# HIVE_dev_sc.net
KiCad netlist of a schematic drawn in EAGLE
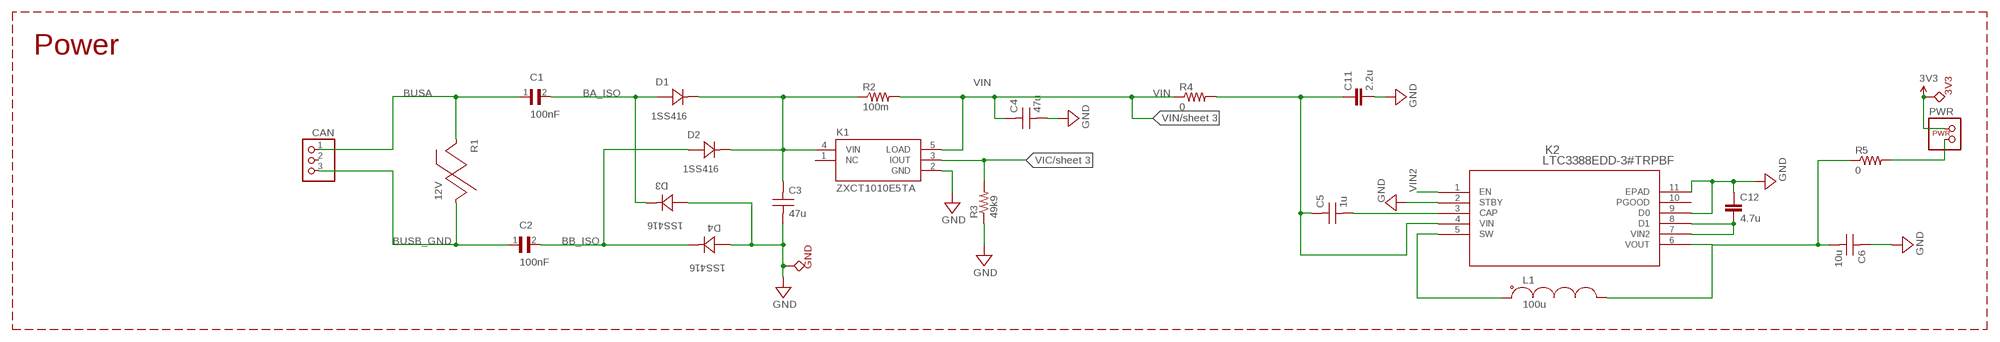
[diagram p0: schematic, sheet 1]
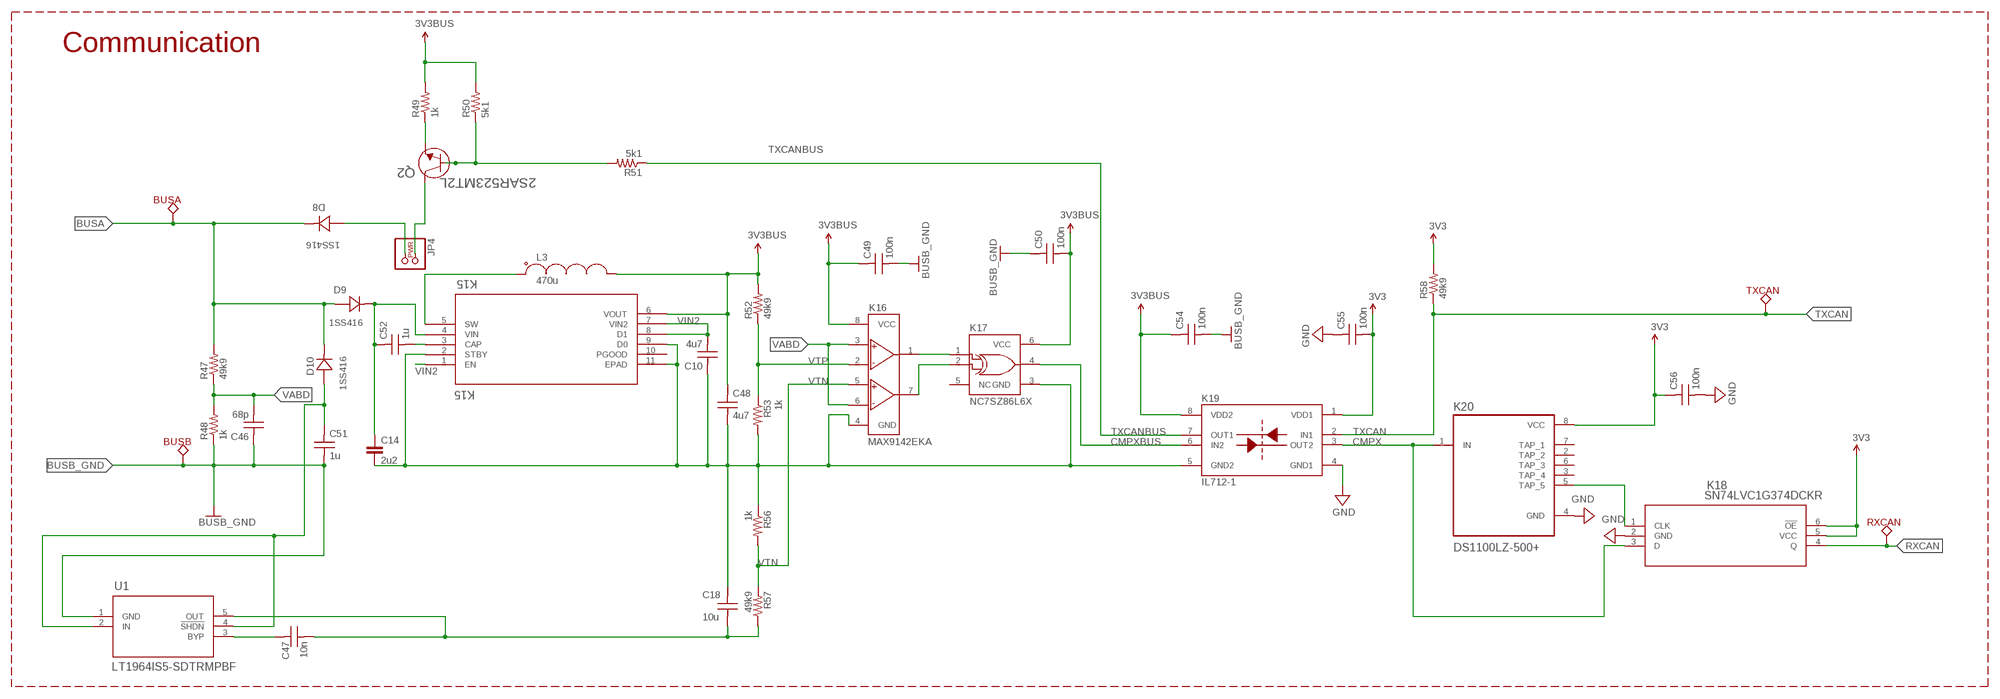
[diagram p1: schematic, sheet 2]
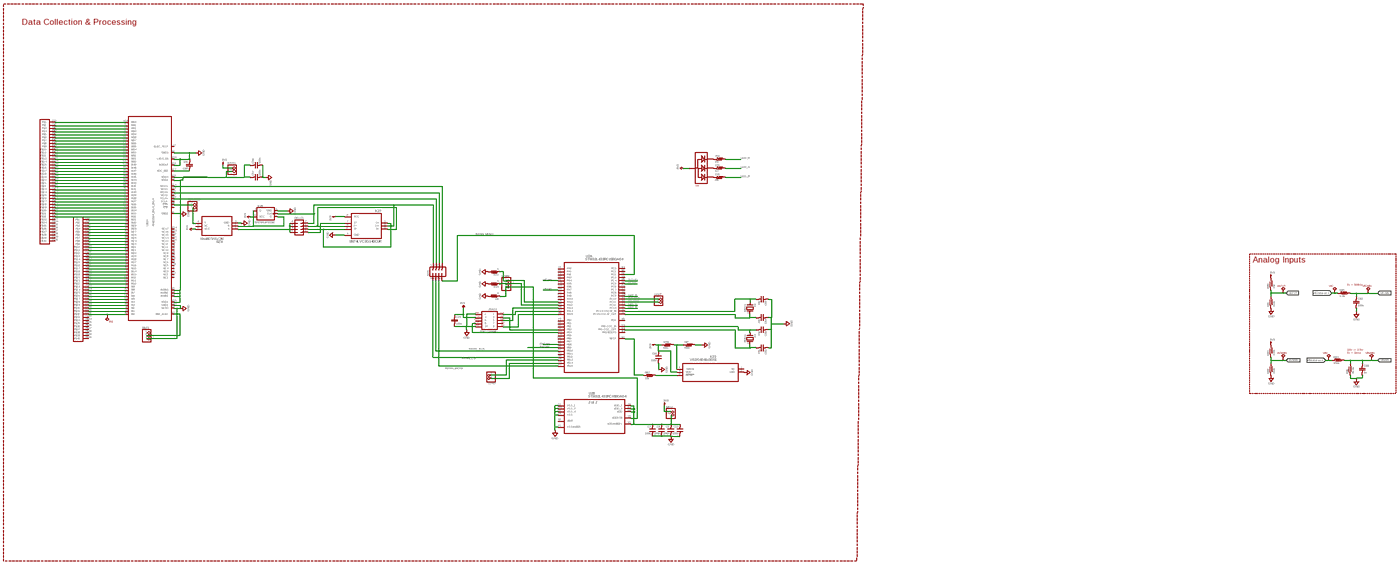
[diagram p2: schematic, sheet 3, overview]
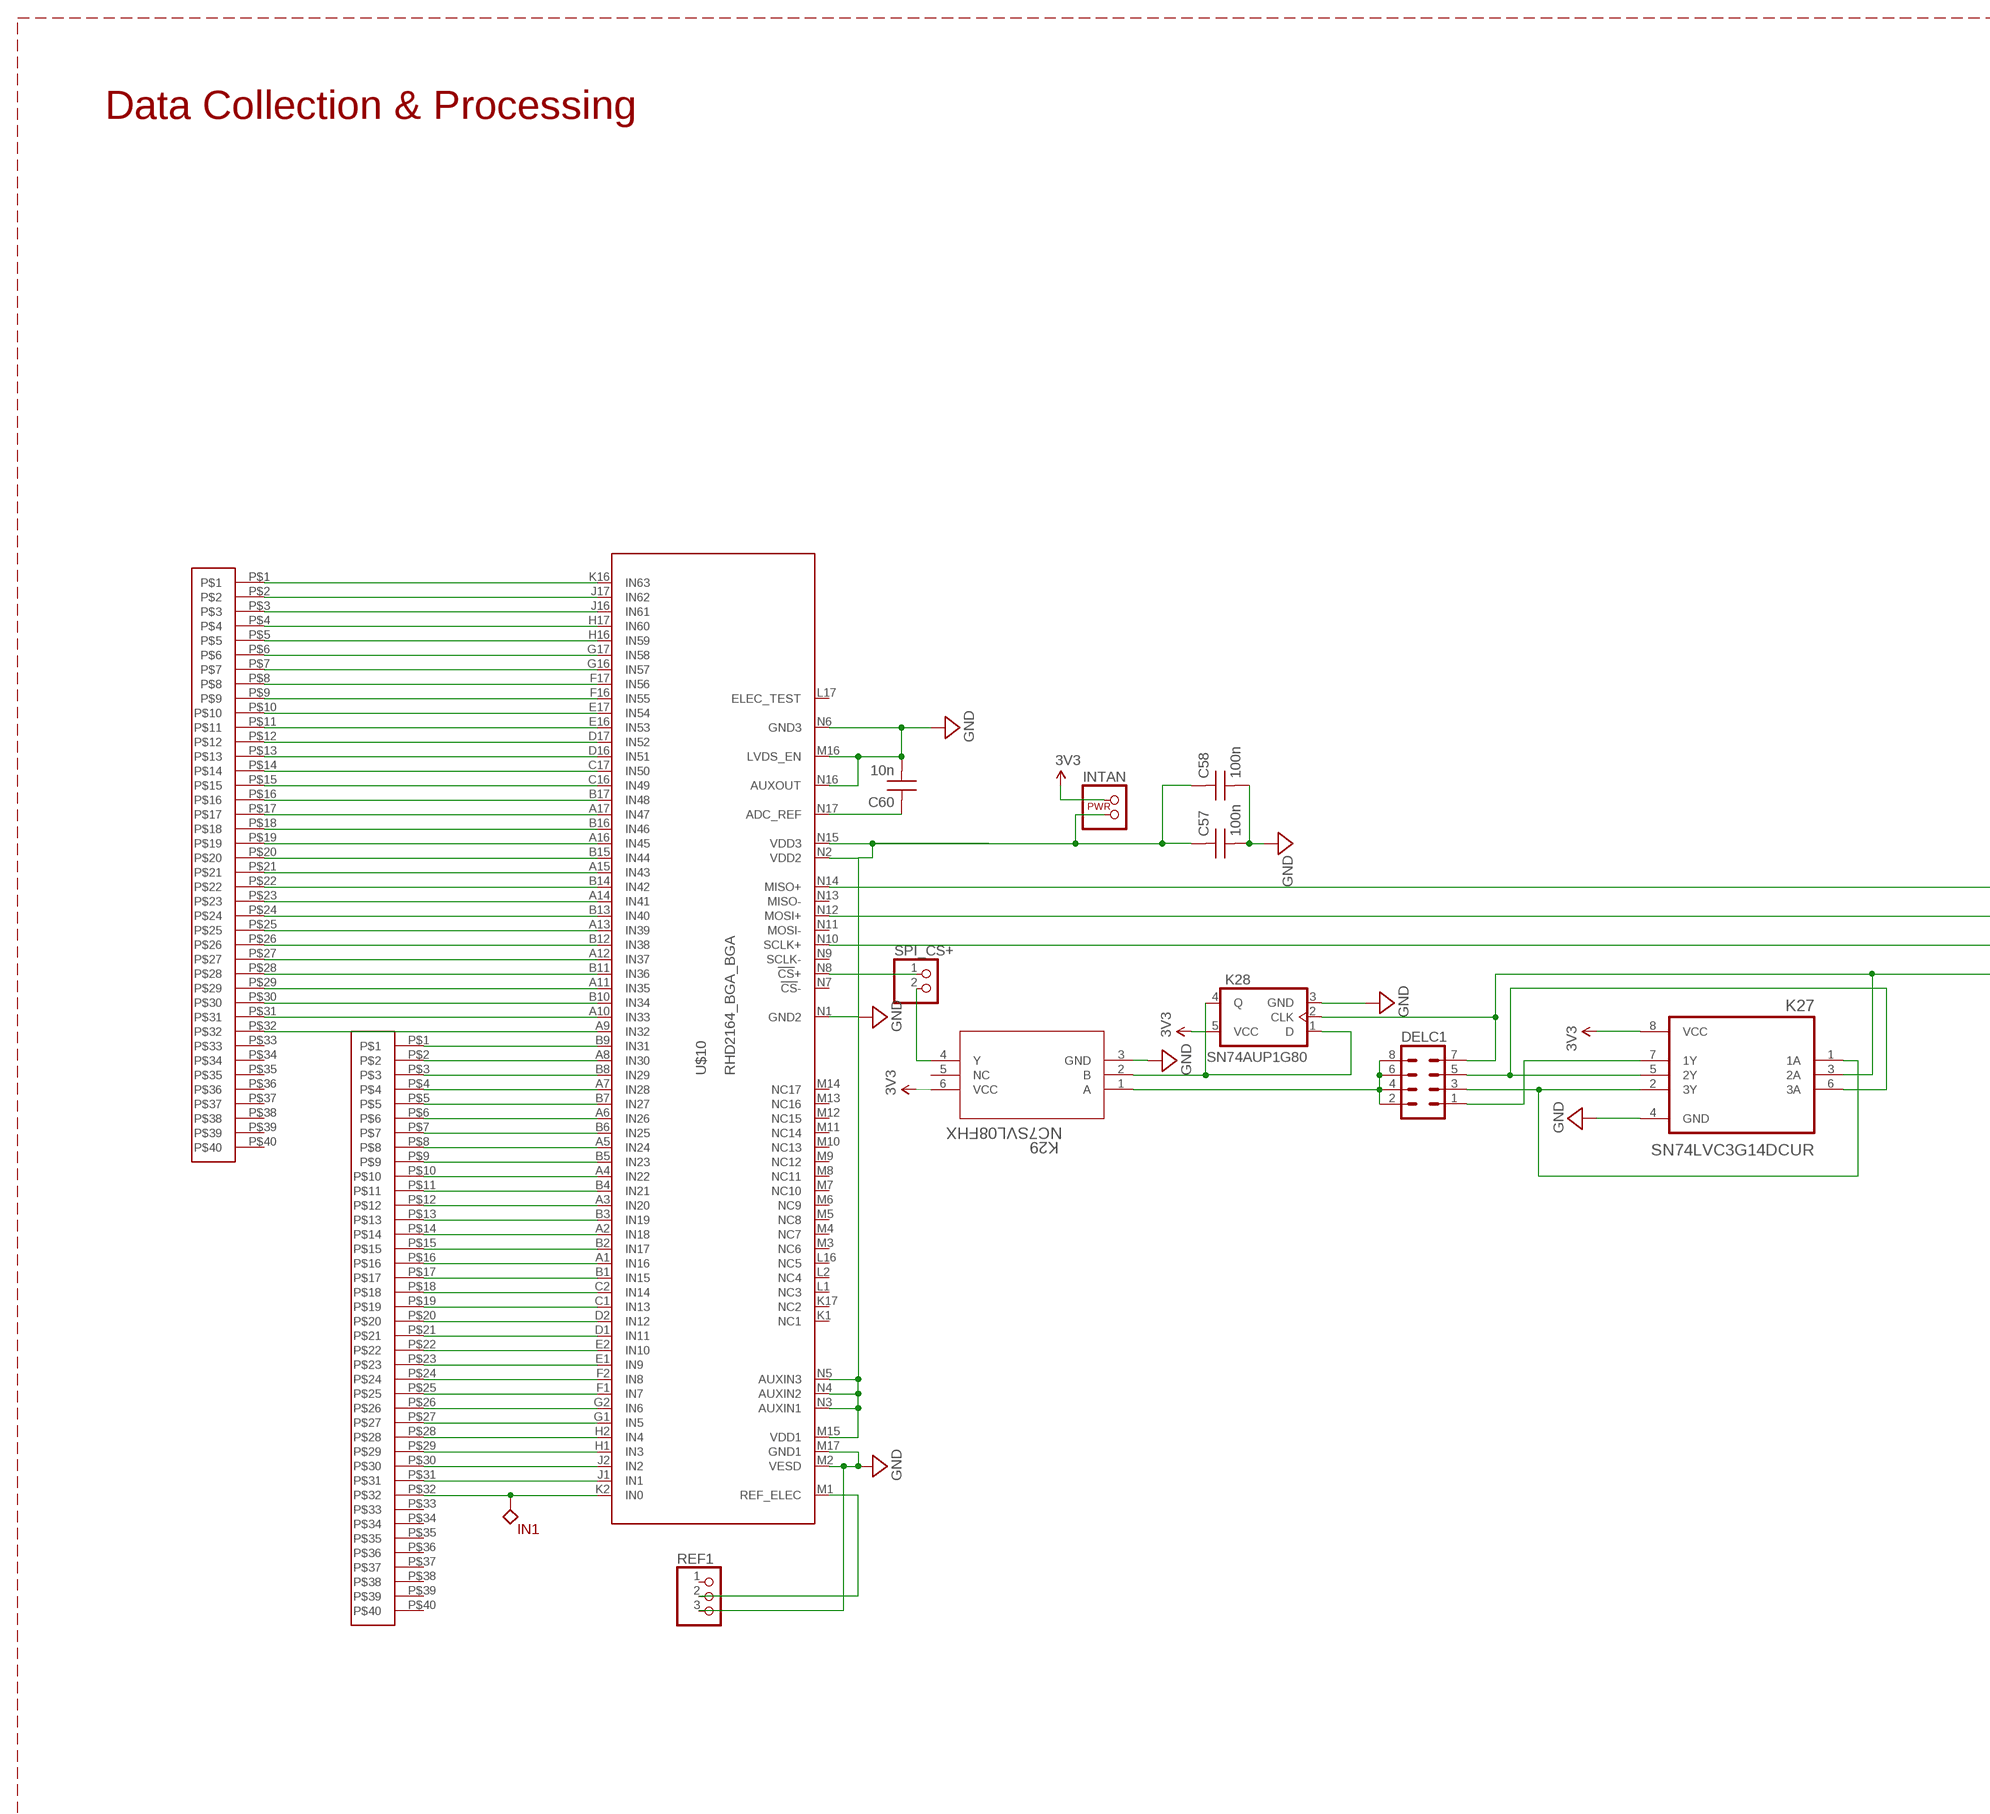
[diagram p3: schematic, sheet 3, part 1 of 5]
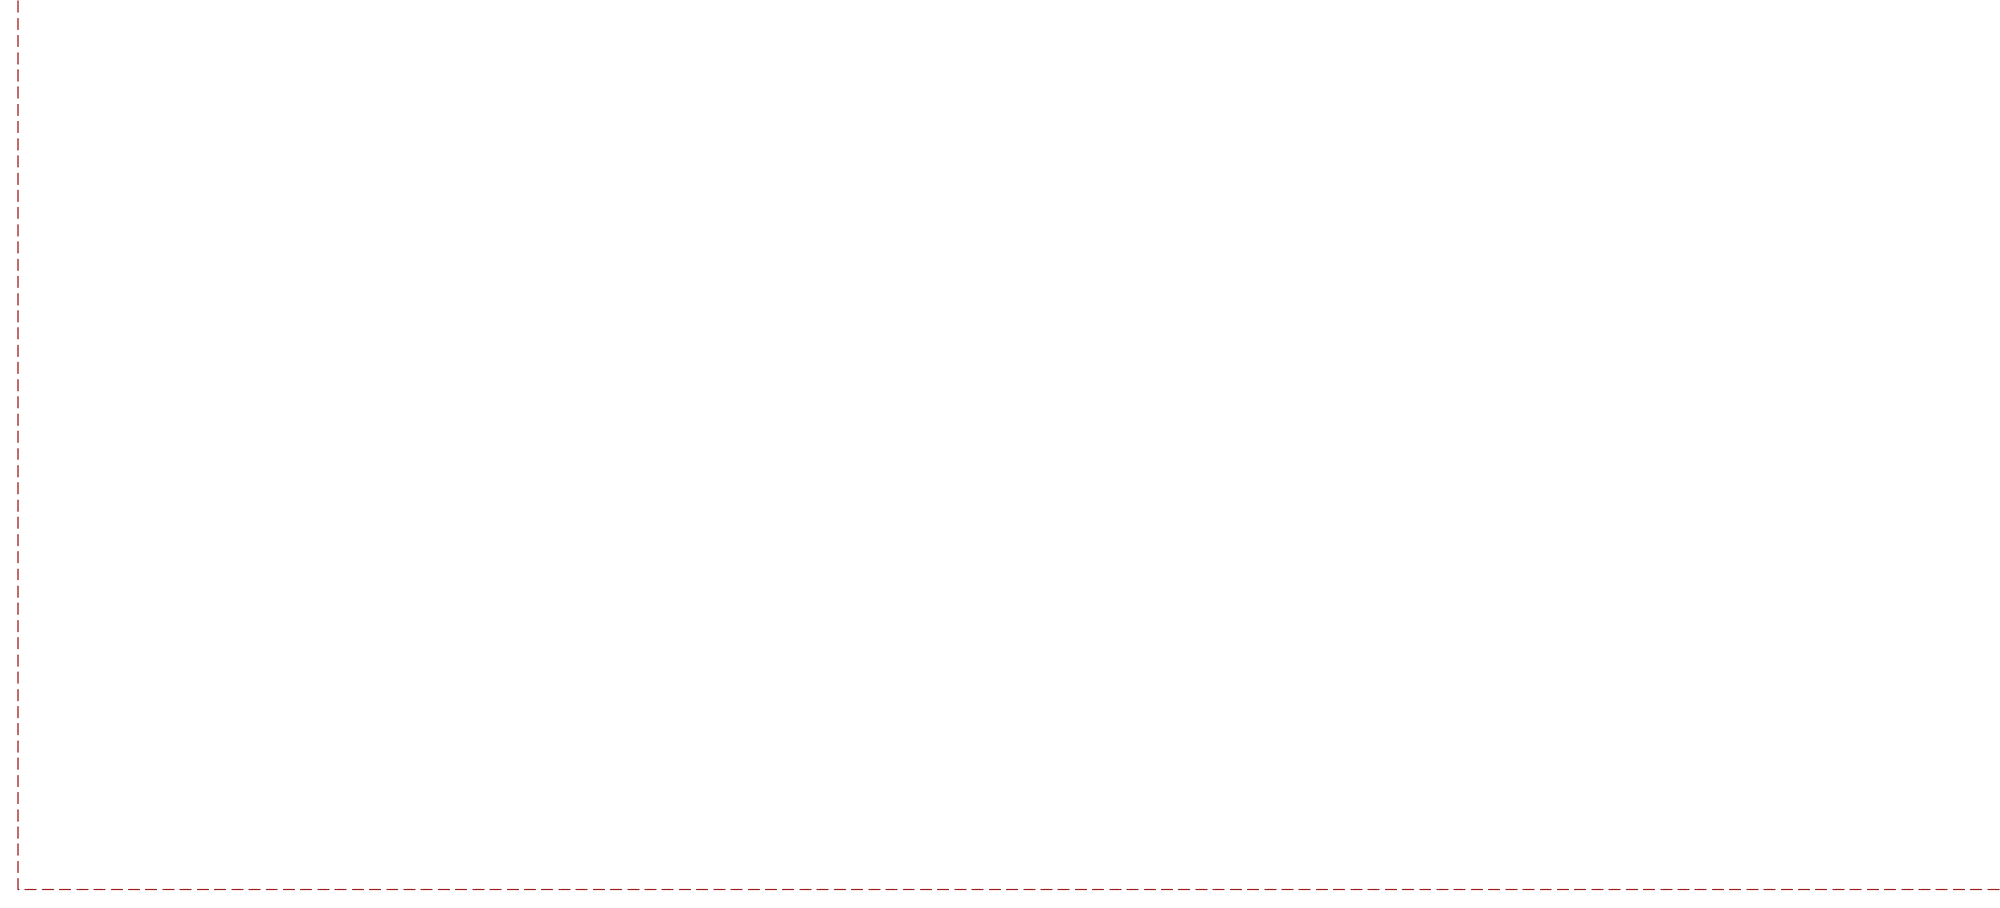
[diagram p4: schematic, sheet 3, part 2 of 5]
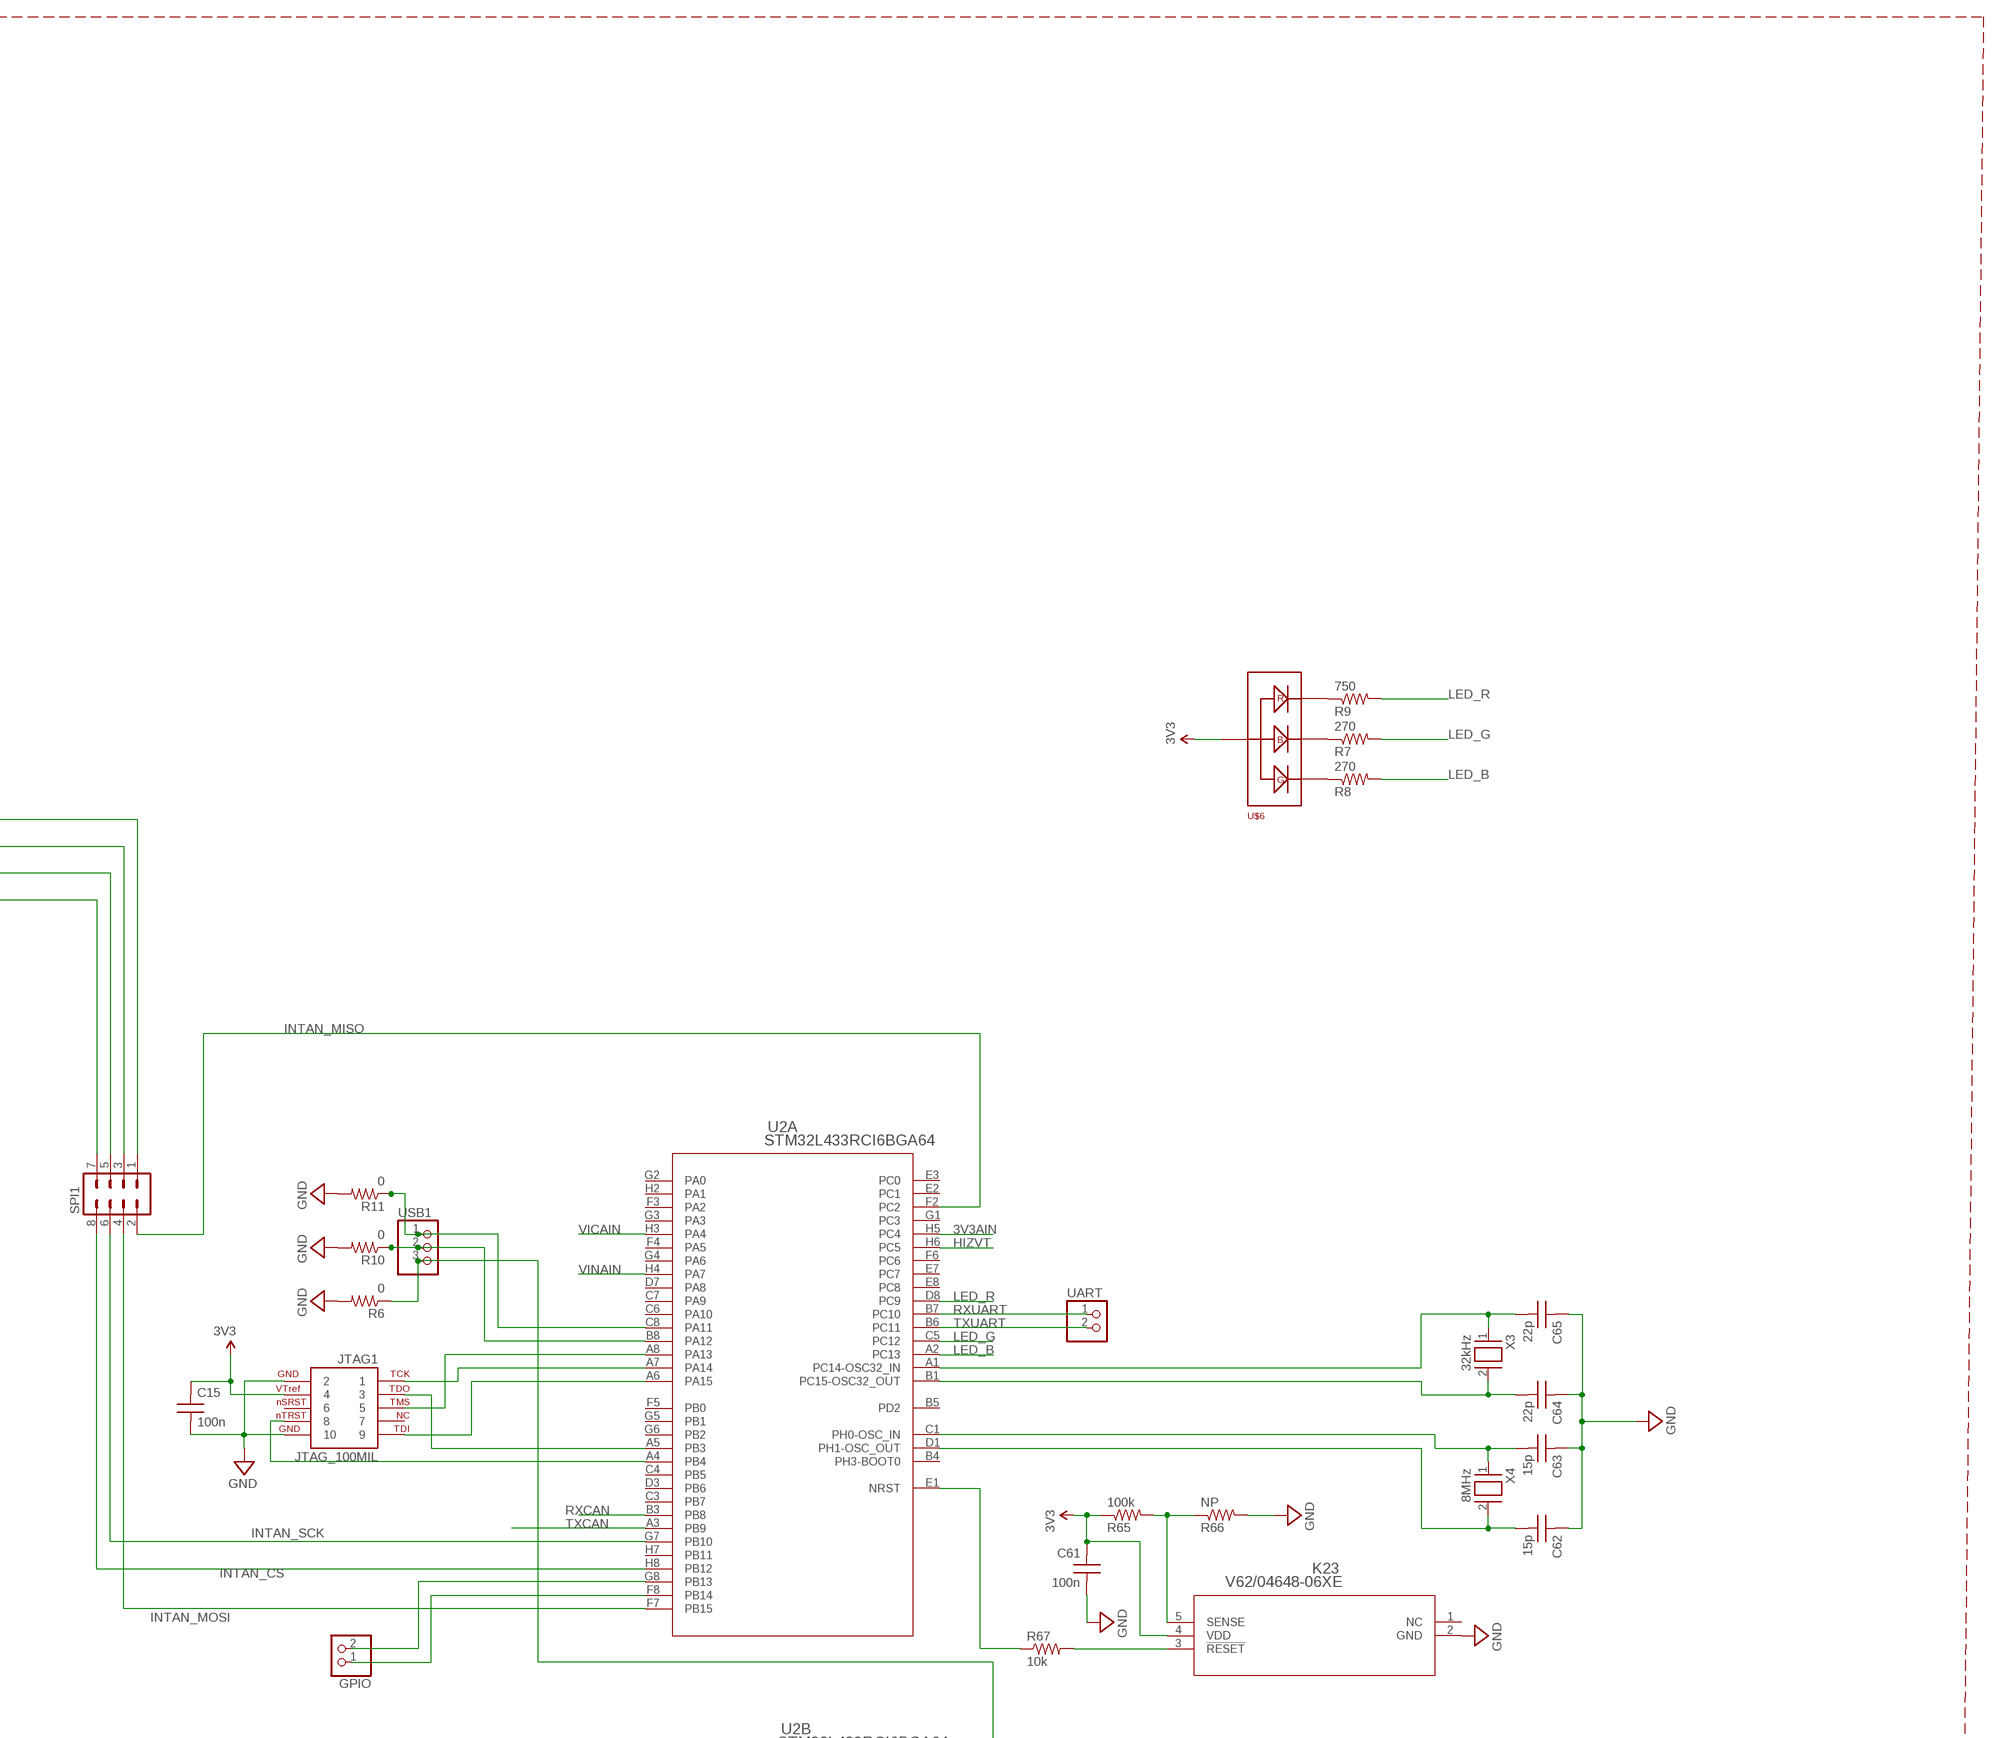
[diagram p5: schematic, sheet 3, part 3 of 5]
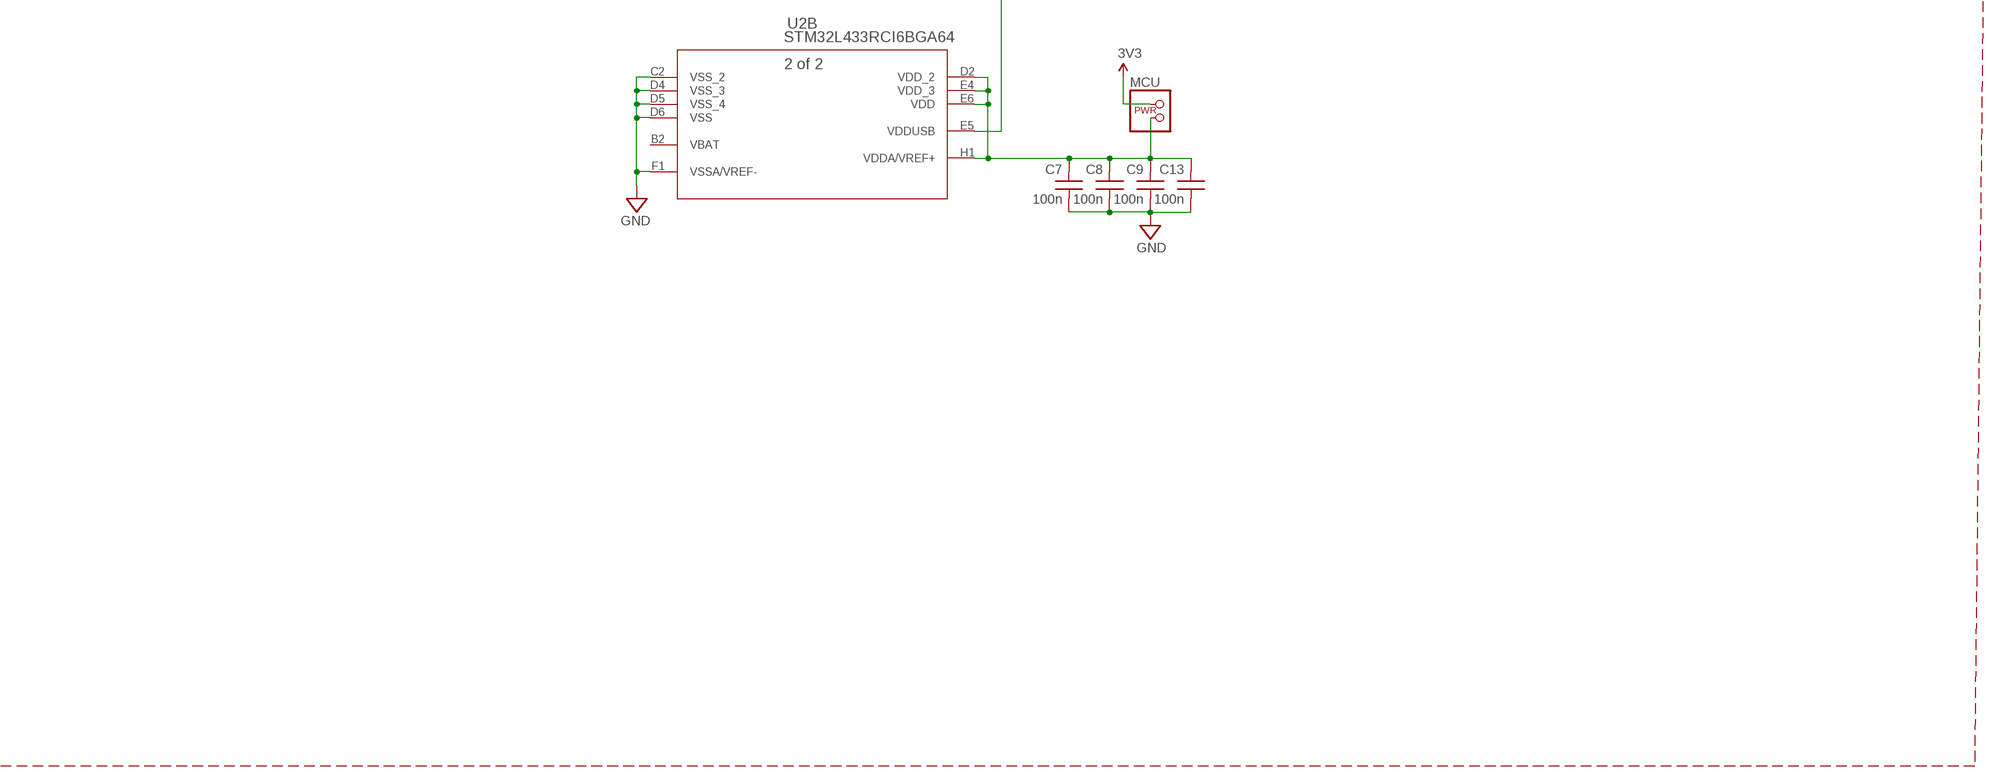
[diagram p6: schematic, sheet 3, part 4 of 5]
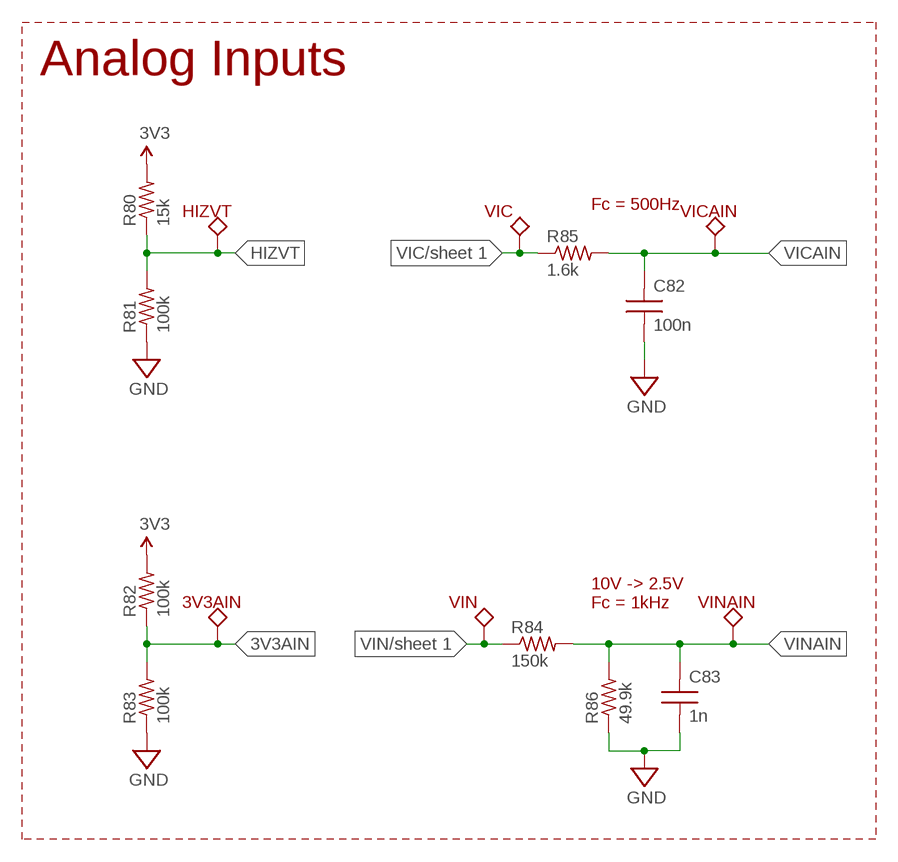
[diagram p7: schematic, sheet 3, part 5 of 5]

(export (version "E")
  (design (tool "Eeschema 10.0.6"))
  (components
    (comp (ref "3V3AIN")
      (value "TPTP5001")
      (footprint "eagle-import:TP5000OR5001")
      (libsource (lib "eagle-import") (part "TPTP5001"))
    )
    (comp (ref "C7")
      (value "100n")
      (footprint "eagle-import:C0201")
      (libsource (lib "eagle-import") (part "C_NPOL_0201"))
    )
    (comp (ref "C8")
      (value "100n")
      (footprint "eagle-import:C0201")
      (libsource (lib "eagle-import") (part "C_NPOL_0201"))
    )
    (comp (ref "C9")
      (value "100n")
      (footprint "eagle-import:C0201")
      (libsource (lib "eagle-import") (part "C_NPOL_0201"))
    )
    (comp (ref "C13")
      (value "100n")
      (footprint "eagle-import:C0201")
      (libsource (lib "eagle-import") (part "C_NPOL_0201"))
    )
    (comp (ref "C15")
      (value "100n")
      (footprint "eagle-import:C0201")
      (libsource (lib "eagle-import") (part "C_NPOL_0201"))
    )
    (comp (ref "C57")
      (value "100n")
      (footprint "eagle-import:C0201")
      (libsource (lib "eagle-import") (part "C_NPOL_0201"))
    )
    (comp (ref "C58")
      (value "100n")
      (footprint "eagle-import:C0201")
      (libsource (lib "eagle-import") (part "C_NPOL_0201"))
    )
    (comp (ref "C60")
      (value "10n")
      (footprint "eagle-import:C0201")
      (libsource (lib "eagle-import") (part "C_NPOL_0201"))
    )
    (comp (ref "C61")
      (value "100n")
      (footprint "eagle-import:C0201")
      (libsource (lib "eagle-import") (part "C_NPOL_0201"))
    )
    (comp (ref "C62")
      (value "15p")
      (footprint "eagle-import:C0402")
      (libsource (lib "eagle-import") (part "C_NPOL_0402"))
    )
    (comp (ref "C63")
      (value "15p")
      (footprint "eagle-import:C0402")
      (libsource (lib "eagle-import") (part "C_NPOL_0402"))
    )
    (comp (ref "C64")
      (value "22p")
      (footprint "eagle-import:C0402")
      (libsource (lib "eagle-import") (part "C_NPOL_0402"))
    )
    (comp (ref "C65")
      (value "22p")
      (footprint "eagle-import:C0402")
      (libsource (lib "eagle-import") (part "C_NPOL_0402"))
    )
    (comp (ref "C82")
      (value "100n")
      (footprint "eagle-import:C0201")
      (libsource (lib "eagle-import") (part "C_NPOL_0201"))
    )
    (comp (ref "C83")
      (value "1n")
      (footprint "eagle-import:C0201")
      (libsource (lib "eagle-import") (part "C_NPOL_0201"))
    )
    (comp (ref "DELC1")
      (value "MA04-2")
      (footprint "eagle-import:MA04-2")
      (libsource (lib "eagle-import") (part "MA04-2"))
    )
    (comp (ref "GPIO")
      (value "PINHD-1X2")
      (footprint "eagle-import:1X02")
      (libsource (lib "eagle-import") (part "PINHD-1X2"))
    )
    (comp (ref "HIZVT")
      (value "TPTP5001")
      (footprint "eagle-import:TP5000OR5001")
      (libsource (lib "eagle-import") (part "TPTP5001"))
    )
    (comp (ref "IN1")
      (value "TPTP5001")
      (footprint "eagle-import:TP5000OR5001")
      (libsource (lib "eagle-import") (part "TPTP5001"))
    )
    (comp (ref "INTAN")
      (value "POWERJUMP")
      (footprint "eagle-import:1X04")
      (libsource (lib "eagle-import") (part "POWERJUMP"))
    )
    (comp (ref "JTAG1")
      (value "JTAG_100MIL")
      (footprint "eagle-import:JTAG-10")
      (libsource (lib "eagle-import") (part "JTAG_100MIL"))
    )
    (comp (ref "K23")
      (value "V62/04648-06XE")
      (footprint "eagle-import:DCK5")
      (fields (field (name "COPYRIGHT") "Copyright (C) 2022 Ultra Librarian. All rights reserved."))
      (libsource (lib "eagle-import") (part "V62/04648-06XE"))
    )
    (comp (ref "K27")
      (value "SN74LVC3G14DCUR")
      (footprint "eagle-import:SOP50P310X90-8N")
      (fields (field (name "DIGI-KEY_PART_NUMBER") "296-13006-2-ND") (field (name "MF") "Texas Instruments"))
      (libsource (lib "eagle-import") (part "SN74LVC3G14DCUR"))
    )
    (comp (ref "K28")
      (value "SN74AUP1G80")
      (footprint "eagle-import:SOT23-5")
      (libsource (lib "eagle-import") (part "SN74AUP1G80"))
    )
    (comp (ref "K29")
      (value "NC7SVL08FHX")
      (footprint "eagle-import:MICROPAK2-6_1X1_ONS")
      (fields (field (name "COPYRIGHT") "Copyright (C) 2022 Ultra Librarian. All rights reserved."))
      (libsource (lib "eagle-import") (part "NC7SVL08FHX"))
    )
    (comp (ref "MCU")
      (value "POWERJUMP")
      (footprint "eagle-import:1X04")
      (libsource (lib "eagle-import") (part "POWERJUMP"))
    )
    (comp (ref "R6")
      (value "0")
      (footprint "eagle-import:R0201")
      (libsource (lib "eagle-import") (part "R_0201"))
    )
    (comp (ref "R7")
      (value "270")
      (footprint "eagle-import:R0201")
      (libsource (lib "eagle-import") (part "R_0201"))
    )
    (comp (ref "R8")
      (value "270")
      (footprint "eagle-import:R0201")
      (libsource (lib "eagle-import") (part "R_0201"))
    )
    (comp (ref "R9")
      (value "750")
      (footprint "eagle-import:R0201")
      (libsource (lib "eagle-import") (part "R_0201"))
    )
    (comp (ref "R10")
      (value "0")
      (footprint "eagle-import:R0201")
      (libsource (lib "eagle-import") (part "R_0201"))
    )
    (comp (ref "R11")
      (value "0")
      (footprint "eagle-import:R0201")
      (libsource (lib "eagle-import") (part "R_0201"))
    )
    (comp (ref "R65")
      (value "100k")
      (footprint "eagle-import:R0201")
      (libsource (lib "eagle-import") (part "R_0201"))
    )
    (comp (ref "R66")
      (value "NP")
      (footprint "eagle-import:R0201")
      (libsource (lib "eagle-import") (part "R_0201"))
    )
    (comp (ref "R67")
      (value "10k")
      (footprint "eagle-import:R0201")
      (libsource (lib "eagle-import") (part "R_0201"))
    )
    (comp (ref "R80")
      (value "15k")
      (footprint "eagle-import:R0201")
      (libsource (lib "eagle-import") (part "R_0201"))
    )
    (comp (ref "R81")
      (value "100k")
      (footprint "eagle-import:R0201")
      (libsource (lib "eagle-import") (part "R_0201"))
    )
    (comp (ref "R82")
      (value "100k")
      (footprint "eagle-import:R0201")
      (libsource (lib "eagle-import") (part "R_0201"))
    )
    (comp (ref "R83")
      (value "100k")
      (footprint "eagle-import:R0201")
      (libsource (lib "eagle-import") (part "R_0201"))
    )
    (comp (ref "R84")
      (value "150k")
      (footprint "eagle-import:R0201")
      (libsource (lib "eagle-import") (part "R_0201"))
    )
    (comp (ref "R85")
      (value "1.6k")
      (footprint "eagle-import:R0201")
      (libsource (lib "eagle-import") (part "R_0201"))
    )
    (comp (ref "R86")
      (value "49.9k")
      (footprint "eagle-import:0201")
      (fields (field (name "MFR") "Panasonic Electronic Components"))
      (libsource (lib "eagle-import") (part "R_0201_49.9K_1/20W_1%"))
    )
    (comp (ref "REF1")
      (value "PINHD-1X3")
      (footprint "eagle-import:1X03")
      (libsource (lib "eagle-import") (part "PINHD-1X3"))
    )
    (comp (ref "SPI1")
      (value "MA04-2")
      (footprint "eagle-import:MA04-2")
      (libsource (lib "eagle-import") (part "MA04-2"))
    )
    (comp (ref "SPI_CS+")
      (value "PINHD-1X2")
      (footprint "eagle-import:1X02")
      (libsource (lib "eagle-import") (part "PINHD-1X2"))
    )
    (comp (ref "U$3")
      (value "40-PIN-SAMTEC")
      (footprint "eagle-import:SAMTECSFH120-01-X-D-SM-LC")
      (libsource (lib "eagle-import") (part "40-PIN-SAMTEC"))
    )
    (comp (ref "U$4")
      (value "40-PIN-SAMTEC")
      (footprint "eagle-import:SAMTECSFH120-01-X-D-SM-LC")
      (libsource (lib "eagle-import") (part "40-PIN-SAMTEC"))
    )
    (comp (ref "U$6")
      (value "WINI_KINGBRIGHT_APHF1608LSEEQBDZGKC")
      (footprint "eagle-import:WINI_4-SMD")
      (libsource (lib "eagle-import") (part "WINI_KINGBRIGHT_APHF1608LSEEQBDZGKC"))
    )
    (comp (ref "U$10")
      (value "RHD2164_BGA_BGA")
      (footprint "eagle-import:BGA104_9X7")
      (libsource (lib "eagle-import") (part "RHD2164_BGA_BGA"))
    )
    (comp (ref "U2")
      (value "STM32L433RCI6BGA64")
      (footprint "eagle-import:BGA64N50P8X8_500X500X60N")
      (libsource (lib "eagle-import") (part "STM32L433RCI6BGA64"))
    )
    (comp (ref "UART")
      (value "PINHD-1X2")
      (footprint "eagle-import:1X02")
      (libsource (lib "eagle-import") (part "PINHD-1X2"))
    )
    (comp (ref "USB1")
      (value "PINHD-1X3")
      (footprint "eagle-import:1X03")
      (libsource (lib "eagle-import") (part "PINHD-1X3"))
    )
    (comp (ref "VIC")
      (value "TPTP5001")
      (footprint "eagle-import:TP5000OR5001")
      (libsource (lib "eagle-import") (part "TPTP5001"))
    )
    (comp (ref "VICAIN")
      (value "TPTP5001")
      (footprint "eagle-import:TP5000OR5001")
      (libsource (lib "eagle-import") (part "TPTP5001"))
    )
    (comp (ref "VIN")
      (value "TPTP5001")
      (footprint "eagle-import:TP5000OR5001")
      (libsource (lib "eagle-import") (part "TPTP5001"))
    )
    (comp (ref "VINAIN")
      (value "TPTP5001")
      (footprint "eagle-import:TP5000OR5001")
      (libsource (lib "eagle-import") (part "TPTP5001"))
    )
    (comp (ref "X3")
      (value "32kHz")
      (footprint "eagle-import:ABS07")
      (libsource (lib "eagle-import") (part "CRYSTAL_ABS07"))
    )
    (comp (ref "X4")
      (value "8MHz")
      (footprint "eagle-import:NX5032GA")
      (libsource (lib "eagle-import") (part "CRYSTAL_NX5032GA"))
    )
    (comp (ref "BUSA")
      (value "TPTP5001")
      (footprint "eagle-import:TP5000OR5001")
      (libsource (lib "eagle-import") (part "TPTP5001"))
    )
    (comp (ref "BUSB")
      (value "TPTP5001")
      (footprint "eagle-import:TP5000OR5001")
      (libsource (lib "eagle-import") (part "TPTP5001"))
    )
    (comp (ref "C10")
      (value "4u7")
      (footprint "eagle-import:C0402")
      (libsource (lib "eagle-import") (part "C_NPOL_0402"))
    )
    (comp (ref "C14")
      (value "2u2")
      (footprint "eagle-import:0402")
      (fields (field (name "MFR") "Murata Electronics"))
      (libsource (lib "eagle-import") (part "C_0402_2.2UF_25V_20%"))
    )
    (comp (ref "C18")
      (value "10u")
      (footprint "eagle-import:C0201")
      (libsource (lib "eagle-import") (part "C_NPOL_0201"))
    )
    (comp (ref "C46")
      (value "68p")
      (footprint "eagle-import:C0201")
      (libsource (lib "eagle-import") (part "C_NPOL_0201"))
    )
    (comp (ref "C47")
      (value "10n")
      (footprint "eagle-import:C0201")
      (libsource (lib "eagle-import") (part "C_NPOL_0201"))
    )
    (comp (ref "C48")
      (value "4u7")
      (footprint "eagle-import:C0402")
      (libsource (lib "eagle-import") (part "C_NPOL_0402"))
    )
    (comp (ref "C49")
      (value "100n")
      (footprint "eagle-import:C0201")
      (libsource (lib "eagle-import") (part "C_NPOL_0201"))
    )
    (comp (ref "C50")
      (value "100n")
      (footprint "eagle-import:C0201")
      (libsource (lib "eagle-import") (part "C_NPOL_0201"))
    )
    (comp (ref "C51")
      (value "1u")
      (footprint "eagle-import:C0201")
      (libsource (lib "eagle-import") (part "C_NPOL_0201"))
    )
    (comp (ref "C52")
      (value "1u")
      (footprint "eagle-import:C0201")
      (libsource (lib "eagle-import") (part "C_NPOL_0201"))
    )
    (comp (ref "C54")
      (value "100n")
      (footprint "eagle-import:C0201")
      (libsource (lib "eagle-import") (part "C_NPOL_0201"))
    )
    (comp (ref "C55")
      (value "100n")
      (footprint "eagle-import:C0201")
      (libsource (lib "eagle-import") (part "C_NPOL_0201"))
    )
    (comp (ref "C56")
      (value "100n")
      (footprint "eagle-import:C0201")
      (libsource (lib "eagle-import") (part "C_NPOL_0201"))
    )
    (comp (ref "D8")
      (value "1SS416")
      (footprint "eagle-import:SOD-923_TOS")
      (fields (field (name "COPYRIGHT") "Copyright (C) 2022 Ultra Librarian. All rights reserved."))
      (libsource (lib "eagle-import") (part "1SS416"))
    )
    (comp (ref "D9")
      (value "1SS416")
      (footprint "eagle-import:SOD-923_TOS")
      (fields (field (name "COPYRIGHT") "Copyright (C) 2022 Ultra Librarian. All rights reserved."))
      (libsource (lib "eagle-import") (part "1SS416"))
    )
    (comp (ref "D10")
      (value "1SS416")
      (footprint "eagle-import:SOD-923_TOS")
      (fields (field (name "COPYRIGHT") "Copyright (C) 2022 Ultra Librarian. All rights reserved."))
      (libsource (lib "eagle-import") (part "1SS416"))
    )
    (comp (ref "JP4")
      (value "POWERJUMP")
      (footprint "eagle-import:1X04")
      (libsource (lib "eagle-import") (part "POWERJUMP"))
    )
    (comp (ref "K15")
      (value "K15")
      (footprint "eagle-import:DFN-10_DD")
      (fields
        (field (name "DIGI-KEY_PART_NUMBER") "LTC3388EDD-3#TRPBFTR-ND")
        (field (name "MF") "Analog Devices")
        (field (name "MP") "LTC3388EDD-3#TRPBF")
      )
      (libsource (lib "eagle-import") (part "LTC3388EDD-3#TRPBF"))
    )
    (comp (ref "K16")
      (value "MAX9142EKA")
      (footprint "eagle-import:SOT23-8")
      (libsource (lib "eagle-import") (part "MAX9142EKA"))
    )
    (comp (ref "K17")
      (value "NC7SZ86L6X")
      (footprint "eagle-import:MAC06A")
      (libsource (lib "eagle-import") (part "NC7SZ86L6X"))
    )
    (comp (ref "K18")
      (value "SN74LVC1G374DCKR")
      (footprint "eagle-import:DCK6")
      (fields (field (name "COPYRIGHT") "Copyright (C) 2023 Ultra Librarian. All rights reserved."))
      (libsource (lib "eagle-import") (part "SN74LVC1G374DCKR"))
    )
    (comp (ref "K19")
      (value "IL712-1")
      (footprint "eagle-import:MSOP-8")
      (libsource (lib "eagle-import") (part "IL712-1"))
    )
    (comp (ref "K20")
      (value "DS1100LZ-500+")
      (footprint "eagle-import:SOIC127P600X175-8N")
      (fields (field (name "DIGI-KEY_PART_NUMBER") "DS1100LZ-500+-ND") (field (name "MF") "Maxim Integrated"))
      (libsource (lib "eagle-import") (part "DS1100LZ-500+"))
    )
    (comp (ref "L3")
      (value "470u")
      (footprint "eagle-import:CB2518")
      (libsource (lib "eagle-import") (part "INDUCTOR_CB2518"))
    )
    (comp (ref "Q2")
      (value "2SAR523MT2L")
      (footprint "eagle-import:TRANS_2SAR522M_ROM")
      (fields (field (name "COPYRIGHT") "Copyright (C) 2022 Ultra Librarian. All rights reserved."))
      (libsource (lib "eagle-import") (part "2SAR523MT2L"))
    )
    (comp (ref "R47")
      (value "49k9")
      (footprint "eagle-import:0201")
      (fields (field (name "MFR") "Panasonic Electronic Components"))
      (libsource (lib "eagle-import") (part "R_0201_49.9K_1/20W_1%"))
    )
    (comp (ref "R48")
      (value "1k")
      (footprint "eagle-import:0201")
      (fields (field (name "MFR") "Panasonic Electronic Components"))
      (libsource (lib "eagle-import") (part "R_0201_1K_1/20W_1%"))
    )
    (comp (ref "R49")
      (value "1k")
      (footprint "eagle-import:0201")
      (fields (field (name "MFR") "Panasonic Electronic Components"))
      (libsource (lib "eagle-import") (part "R_0201_1K_1/20W_1%"))
    )
    (comp (ref "R50")
      (value "5k1")
      (footprint "eagle-import:0201")
      (fields (field (name "MFR") "Panasonic Electronic Components"))
      (libsource (lib "eagle-import") (part "R_0201_5.1K_1/20W_5%"))
    )
    (comp (ref "R51")
      (value "5k1")
      (footprint "eagle-import:0201")
      (fields (field (name "MFR") "Panasonic Electronic Components"))
      (libsource (lib "eagle-import") (part "R_0201_5.1K_1/20W_5%"))
    )
    (comp (ref "R52")
      (value "49k9")
      (footprint "eagle-import:0201")
      (fields (field (name "MFR") "Panasonic Electronic Components"))
      (libsource (lib "eagle-import") (part "R_0201_49.9K_1/20W_1%"))
    )
    (comp (ref "R53")
      (value "1k")
      (footprint "eagle-import:0201")
      (fields (field (name "MFR") "Panasonic Electronic Components"))
      (libsource (lib "eagle-import") (part "R_0201_1K_1/20W_1%"))
    )
    (comp (ref "R56")
      (value "1k")
      (footprint "eagle-import:0201")
      (fields (field (name "MFR") "Panasonic Electronic Components"))
      (libsource (lib "eagle-import") (part "R_0201_1K_1/20W_1%"))
    )
    (comp (ref "R57")
      (value "49k9")
      (footprint "eagle-import:0201")
      (fields (field (name "MFR") "Panasonic Electronic Components"))
      (libsource (lib "eagle-import") (part "R_0201_49.9K_1/20W_1%"))
    )
    (comp (ref "R58")
      (value "49k9")
      (footprint "eagle-import:0201")
      (fields (field (name "MFR") "Panasonic Electronic Components"))
      (libsource (lib "eagle-import") (part "R_0201_49.9K_1/20W_1%"))
    )
    (comp (ref "RXCAN")
      (value "TPTP5001")
      (footprint "eagle-import:TP5000OR5001")
      (libsource (lib "eagle-import") (part "TPTP5001"))
    )
    (comp (ref "TXCAN")
      (value "TPTP5001")
      (footprint "eagle-import:TP5000OR5001")
      (libsource (lib "eagle-import") (part "TPTP5001"))
    )
    (comp (ref "U1")
      (value "LT1964IS5-SDTRMPBF")
      (footprint "eagle-import:TSOT23-5_S5_ADI")
      (fields
        (field (name "MANUFACTURER_PART_NUMBER") "LT1964IS5-SD#TRMPBF")
        (field (name "COPYRIGHT") "Copyright (C) 2022 Ultra Librarian. All rights reserved.")
      )
      (libsource (lib "eagle-import") (part "LT1964IS5-SDTRMPBF"))
    )
    (comp (ref "3V3")
      (value "TPTP5001")
      (footprint "eagle-import:TP5000OR5001")
      (libsource (lib "eagle-import") (part "TPTP5001"))
    )
    (comp (ref "C1")
      (value "100nF")
      (footprint "eagle-import:CAPC1005X55N")
      (fields
        (field (name "DIGI-KEY_PART_NUMBER") "587-3499-2-ND")
        (field (name "MF") "Taiyo Yuden")
        (field (name "MP") "UMK105BJ104KV-F")
      )
      (libsource (lib "eagle-import") (part "UMK105BJ104KV-F"))
    )
    (comp (ref "C2")
      (value "100nF")
      (footprint "eagle-import:CAPC1005X55N")
      (fields
        (field (name "DIGI-KEY_PART_NUMBER") "587-3499-2-ND")
        (field (name "MF") "Taiyo Yuden")
        (field (name "MP") "UMK105BJ104KV-F")
      )
      (libsource (lib "eagle-import") (part "UMK105BJ104KV-F"))
    )
    (comp (ref "C3")
      (value "47u")
      (footprint "eagle-import:C0603")
      (libsource (lib "eagle-import") (part "C_NPOL_0603"))
    )
    (comp (ref "C4")
      (value "47u")
      (footprint "eagle-import:C0603")
      (libsource (lib "eagle-import") (part "C_NPOL_0603"))
    )
    (comp (ref "C5")
      (value "1u")
      (footprint "eagle-import:C0201")
      (libsource (lib "eagle-import") (part "C_NPOL_0201"))
    )
    (comp (ref "C6")
      (value "10u")
      (footprint "eagle-import:C0603")
      (libsource (lib "eagle-import") (part "C_NPOL_0603"))
    )
    (comp (ref "C11")
      (value "2.2u")
      (footprint "eagle-import:0402")
      (fields (field (name "MFR") "Murata Electronics"))
      (libsource (lib "eagle-import") (part "C_0402_2.2UF_25V_20%"))
    )
    (comp (ref "C12")
      (value "4.7u")
      (footprint "eagle-import:0402")
      (fields (field (name "MFR") "Murata Electronics"))
      (libsource (lib "eagle-import") (part "C_0402_4.7UF_6.3V_20%"))
    )
    (comp (ref "CAN")
      (value "PINHD-1X3")
      (footprint "eagle-import:1X03")
      (libsource (lib "eagle-import") (part "PINHD-1X3"))
    )
    (comp (ref "D1")
      (value "1SS416")
      (footprint "eagle-import:SOD-923_TOS")
      (fields (field (name "COPYRIGHT") "Copyright (C) 2022 Ultra Librarian. All rights reserved."))
      (libsource (lib "eagle-import") (part "1SS416"))
    )
    (comp (ref "D2")
      (value "1SS416")
      (footprint "eagle-import:SOD-923_TOS")
      (fields (field (name "COPYRIGHT") "Copyright (C) 2022 Ultra Librarian. All rights reserved."))
      (libsource (lib "eagle-import") (part "1SS416"))
    )
    (comp (ref "D3")
      (value "1SS416")
      (footprint "eagle-import:SOD-923_TOS")
      (fields (field (name "COPYRIGHT") "Copyright (C) 2022 Ultra Librarian. All rights reserved."))
      (libsource (lib "eagle-import") (part "1SS416"))
    )
    (comp (ref "D4")
      (value "1SS416")
      (footprint "eagle-import:SOD-923_TOS")
      (fields (field (name "COPYRIGHT") "Copyright (C) 2022 Ultra Librarian. All rights reserved."))
      (libsource (lib "eagle-import") (part "1SS416"))
    )
    (comp (ref "GND")
      (value "TPTP5001")
      (footprint "eagle-import:TP5000OR5001")
      (libsource (lib "eagle-import") (part "TPTP5001"))
    )
    (comp (ref "K1")
      (value "ZXCT1010E5TA")
      (footprint "eagle-import:SOT25")
      (libsource (lib "eagle-import") (part "ZXCT1010E5TA"))
    )
    (comp (ref "K2")
      (value "LTC3388EDD-3#TRPBF")
      (footprint "eagle-import:DFN-10_DD")
      (fields
        (field (name "DIGI-KEY_PART_NUMBER") "LTC3388EDD-3#TRPBFTR-ND")
        (field (name "MF") "Analog Devices")
      )
      (libsource (lib "eagle-import") (part "LTC3388EDD-3#TRPBF"))
    )
    (comp (ref "L1")
      (value "100u")
      (footprint "eagle-import:LPS4414")
      (libsource (lib "eagle-import") (part "INDUCTOR_LPS4414"))
    )
    (comp (ref "PWR")
      (value "POWERJUMP")
      (footprint "eagle-import:1X04")
      (libsource (lib "eagle-import") (part "POWERJUMP"))
    )
    (comp (ref "R1")
      (value "12V")
      (footprint "eagle-import:CG0603MLC")
      (libsource (lib "eagle-import") (part "CG0603MLC"))
    )
    (comp (ref "R2")
      (value "100m")
      (footprint "eagle-import:R0201")
      (libsource (lib "eagle-import") (part "R_0201"))
    )
    (comp (ref "R3")
      (value "49k9")
      (footprint "eagle-import:0201")
      (fields (field (name "MFR") "Panasonic Electronic Components"))
      (libsource (lib "eagle-import") (part "R_0201_49.9K_1/20W_1%"))
    )
    (comp (ref "R4")
      (value "0")
      (footprint "eagle-import:R0201")
      (libsource (lib "eagle-import") (part "R_0201"))
    )
    (comp (ref "R5")
      (value "0")
      (footprint "eagle-import:R0201")
      (libsource (lib "eagle-import") (part "R_0201"))
    )
  )
  (nets
    (net (code "1") (name "3V3") (class "Default")
      (node (ref "3V3") (pin "P$1") (pinfunction "P$1_P$1") (pintype "passive"))
      (node (ref "C15") (pin "2") (pinfunction "P$2_2") (pintype "bidirectional"))
      (node (ref "C55") (pin "1") (pinfunction "P$1_1") (pintype "bidirectional"))
      (node (ref "C56") (pin "2") (pinfunction "P$2_2") (pintype "bidirectional"))
      (node (ref "C61") (pin "2") (pinfunction "P$2_2") (pintype "bidirectional"))
      (node (ref "INTAN") (pin "1") (pinfunction "1_1") (pintype "passive"))
      (node (ref "INTAN") (pin "2") (pinfunction "1_2") (pintype "passive"))
      (node (ref "JTAG1") (pin "4") (pinfunction "4_4") (pintype "bidirectional"))
      (node (ref "K18") (pin "5") (pinfunction "VCC_5") (pintype "power_in"))
      (node (ref "K18") (pin "6") (pinfunction "~{OE}_6") (pintype "input"))
      (node (ref "K19") (pin "1") (pinfunction "VDD1_1") (pintype "bidirectional"))
      (node (ref "K20") (pin "8") (pinfunction "VCC_8") (pintype "power_in"))
      (node (ref "K23") (pin "4") (pinfunction "VDD_4") (pintype "power_in"))
      (node (ref "K27") (pin "8") (pinfunction "VCC_8") (pintype "power_in"))
      (node (ref "K28") (pin "5") (pinfunction "VCC_5") (pintype "bidirectional"))
      (node (ref "MCU") (pin "1") (pinfunction "1_1") (pintype "passive"))
      (node (ref "MCU") (pin "2") (pinfunction "1_2") (pintype "passive"))
      (node (ref "PWR") (pin "1") (pinfunction "1_1") (pintype "passive"))
      (node (ref "PWR") (pin "2") (pinfunction "1_2") (pintype "passive"))
      (node (ref "R58") (pin "2") (pinfunction "2_2") (pintype "passive"))
      (node (ref "R65") (pin "1") (pinfunction "1_1") (pintype "passive"))
      (node (ref "R80") (pin "2") (pinfunction "2_2") (pintype "passive"))
      (node (ref "R82") (pin "2") (pinfunction "2_2") (pintype "passive"))
      (node (ref "U$6") (pin "V+") (pinfunction "V+_V+") (pintype "passive"))
    )
    (net (code "2") (name "3V3AIN") (class "Default")
      (node (ref "3V3AIN") (pin "P$1") (pinfunction "P$1_P$1") (pintype "passive"))
      (node (ref "R82") (pin "1") (pinfunction "1_1") (pintype "passive"))
      (node (ref "R83") (pin "2") (pinfunction "2_2") (pintype "passive"))
      (node (ref "U2") (pin "H5") (pinfunction "PC4_H5") (pintype "bidirectional"))
    )
    (net (code "3") (name "3V3BUS") (class "Default")
      (node (ref "C48") (pin "2") (pinfunction "P$2_2") (pintype "bidirectional"))
      (node (ref "C49") (pin "2") (pinfunction "P$2_2") (pintype "bidirectional"))
      (node (ref "C50") (pin "1") (pinfunction "P$1_1") (pintype "bidirectional"))
      (node (ref "C54") (pin "2") (pinfunction "P$2_2") (pintype "bidirectional"))
      (node (ref "K15") (pin "6") (pinfunction "VOUT_6") (pintype "output"))
      (node (ref "K16") (pin "8") (pinfunction "VCC_8") (pintype "bidirectional"))
      (node (ref "K17") (pin "6") (pinfunction "VCC_6") (pintype "bidirectional"))
      (node (ref "K19") (pin "8") (pinfunction "VDD2_8") (pintype "bidirectional"))
      (node (ref "L3") (pin "2") (pinfunction "P$1_2") (pintype "bidirectional"))
      (node (ref "R49") (pin "2") (pinfunction "2_2") (pintype "passive"))
      (node (ref "R50") (pin "2") (pinfunction "2_2") (pintype "passive"))
      (node (ref "R52") (pin "2") (pinfunction "2_2") (pintype "passive"))
    )
    (net (code "4") (name "BA_ISO") (class "Default")
      (node (ref "C1") (pin "2") (pinfunction "2_2") (pintype "passive"))
      (node (ref "D1") (pin "2") (pinfunction "ANODE_2") (pintype "passive"))
      (node (ref "D3") (pin "1") (pinfunction "CATHODE_1") (pintype "passive"))
    )
    (net (code "5") (name "BB_ISO") (class "Default")
      (node (ref "C2") (pin "2") (pinfunction "2_2") (pintype "passive"))
      (node (ref "D2") (pin "2") (pinfunction "ANODE_2") (pintype "passive"))
      (node (ref "D4") (pin "1") (pinfunction "CATHODE_1") (pintype "passive"))
    )
    (net (code "6") (name "BUSA") (class "Default")
      (node (ref "BUSA") (pin "P$1") (pinfunction "P$1_P$1") (pintype "passive"))
      (node (ref "C1") (pin "1") (pinfunction "1_1") (pintype "passive"))
      (node (ref "CAN") (pin "1") (pinfunction "1_1") (pintype "passive"))
      (node (ref "D10") (pin "1") (pinfunction "CATHODE_1") (pintype "passive"))
      (node (ref "D8") (pin "1") (pinfunction "CATHODE_1") (pintype "passive"))
      (node (ref "D9") (pin "2") (pinfunction "ANODE_2") (pintype "passive"))
      (node (ref "R1") (pin "1") (pinfunction "P$1_1") (pintype "bidirectional"))
      (node (ref "R47") (pin "2") (pinfunction "2_2") (pintype "passive"))
    )
    (net (code "7") (name "BUSB_GND") (class "Default")
      (node (ref "BUSB") (pin "P$1") (pinfunction "P$1_P$1") (pintype "passive"))
      (node (ref "C2") (pin "1") (pinfunction "1_1") (pintype "passive"))
      (node (ref "C46") (pin "2") (pinfunction "P$2_2") (pintype "bidirectional"))
      (node (ref "C49") (pin "1") (pinfunction "P$1_1") (pintype "bidirectional"))
      (node (ref "C50") (pin "2") (pinfunction "P$2_2") (pintype "bidirectional"))
      (node (ref "C51") (pin "1") (pinfunction "P$1_1") (pintype "bidirectional"))
      (node (ref "C54") (pin "1") (pinfunction "P$1_1") (pintype "bidirectional"))
      (node (ref "CAN") (pin "3") (pinfunction "3_3") (pintype "passive"))
      (node (ref "R1") (pin "2") (pinfunction "P$2_2") (pintype "bidirectional"))
      (node (ref "R48") (pin "1") (pinfunction "1_1") (pintype "passive"))
      (node (ref "U1") (pin "1") (pinfunction "GND_1") (pintype "passive"))
    )
    (net (code "8") (name "CMPX") (class "Default")
      (node (ref "K18") (pin "3") (pinfunction "D_3") (pintype "input"))
      (node (ref "K19") (pin "3") (pinfunction "OUT2_3") (pintype "bidirectional"))
      (node (ref "K20") (pin "1") (pinfunction "IN_1") (pintype "input"))
    )
    (net (code "9") (name "CMPXBUS") (class "Default")
      (node (ref "K17") (pin "4") (pinfunction "Y_4") (pintype "bidirectional"))
      (node (ref "K19") (pin "6") (pinfunction "IN2_6") (pintype "bidirectional"))
    )
    (net (code "10") (name "GND") (class "Default")
      (node (ref "C11") (pin "2") (pinfunction "2_2") (pintype "passive"))
      (node (ref "C12") (pin "1") (pinfunction "1_1") (pintype "passive"))
      (node (ref "C13") (pin "1") (pinfunction "P$1_1") (pintype "bidirectional"))
      (node (ref "C15") (pin "1") (pinfunction "P$1_1") (pintype "bidirectional"))
      (node (ref "C3") (pin "1") (pinfunction "P$1_1") (pintype "bidirectional"))
      (node (ref "C4") (pin "1") (pinfunction "P$1_1") (pintype "bidirectional"))
      (node (ref "C55") (pin "2") (pinfunction "P$2_2") (pintype "bidirectional"))
      (node (ref "C56") (pin "1") (pinfunction "P$1_1") (pintype "bidirectional"))
      (node (ref "C57") (pin "1") (pinfunction "P$1_1") (pintype "bidirectional"))
      (node (ref "C58") (pin "1") (pinfunction "P$1_1") (pintype "bidirectional"))
      (node (ref "C6") (pin "2") (pinfunction "P$2_2") (pintype "bidirectional"))
      (node (ref "C60") (pin "1") (pinfunction "P$1_1") (pintype "bidirectional"))
      (node (ref "C61") (pin "1") (pinfunction "P$1_1") (pintype "bidirectional"))
      (node (ref "C62") (pin "2") (pinfunction "P$2_2") (pintype "bidirectional"))
      (node (ref "C63") (pin "2") (pinfunction "P$2_2") (pintype "bidirectional"))
      (node (ref "C64") (pin "2") (pinfunction "P$2_2") (pintype "bidirectional"))
      (node (ref "C65") (pin "2") (pinfunction "P$2_2") (pintype "bidirectional"))
      (node (ref "C7") (pin "1") (pinfunction "P$1_1") (pintype "bidirectional"))
      (node (ref "C8") (pin "1") (pinfunction "P$1_1") (pintype "bidirectional"))
      (node (ref "C82") (pin "1") (pinfunction "P$1_1") (pintype "bidirectional"))
      (node (ref "C83") (pin "1") (pinfunction "P$1_1") (pintype "bidirectional"))
      (node (ref "C9") (pin "1") (pinfunction "P$1_1") (pintype "bidirectional"))
      (node (ref "D3") (pin "2") (pinfunction "ANODE_2") (pintype "passive"))
      (node (ref "D4") (pin "2") (pinfunction "ANODE_2") (pintype "passive"))
      (node (ref "GND") (pin "P$1") (pinfunction "P$1_P$1") (pintype "passive"))
      (node (ref "JTAG1") (pin "10") (pinfunction "10_10") (pintype "bidirectional"))
      (node (ref "JTAG1") (pin "2") (pinfunction "2_2") (pintype "bidirectional"))
      (node (ref "K1") (pin "2") (pinfunction "GND_2") (pintype "bidirectional"))
      (node (ref "K18") (pin "2") (pinfunction "GND_2") (pintype "power_in"))
      (node (ref "K19") (pin "4") (pinfunction "GND1_4") (pintype "bidirectional"))
      (node (ref "K2") (pin "11") (pinfunction "EPAD_11") (pintype "passive"))
      (node (ref "K2") (pin "2") (pinfunction "STBY_2") (pintype "input"))
      (node (ref "K2") (pin "9") (pinfunction "D0_9") (pintype "output"))
      (node (ref "K20") (pin "4") (pinfunction "GND_4") (pintype "power_in"))
      (node (ref "K23") (pin "2") (pinfunction "GND_2") (pintype "power_in"))
      (node (ref "K27") (pin "4") (pinfunction "GND_4") (pintype "power_in"))
      (node (ref "K28") (pin "3") (pinfunction "GND_3") (pintype "bidirectional"))
      (node (ref "K29") (pin "3") (pinfunction "GND_3") (pintype "passive"))
      (node (ref "R10") (pin "2") (pinfunction "2_2") (pintype "passive"))
      (node (ref "R11") (pin "2") (pinfunction "2_2") (pintype "passive"))
      (node (ref "R3") (pin "1") (pinfunction "1_1") (pintype "passive"))
      (node (ref "R6") (pin "2") (pinfunction "2_2") (pintype "passive"))
      (node (ref "R66") (pin "2") (pinfunction "2_2") (pintype "passive"))
      (node (ref "R81") (pin "1") (pinfunction "1_1") (pintype "passive"))
      (node (ref "R83") (pin "1") (pinfunction "1_1") (pintype "passive"))
      (node (ref "R86") (pin "1") (pinfunction "1_1") (pintype "passive"))
      (node (ref "REF1") (pin "3") (pinfunction "3_3") (pintype "passive"))
      (node (ref "U$10") (pin "M16") (pinfunction "LVDS_EN_M16") (pintype "input"))
      (node (ref "U$10") (pin "M17") (pinfunction "GND1_M17") (pintype "power_in"))
      (node (ref "U$10") (pin "M2") (pinfunction "VESD_M2") (pintype "power_in"))
      (node (ref "U$10") (pin "N1") (pinfunction "GND2_N1") (pintype "power_in"))
      (node (ref "U$10") (pin "N16") (pinfunction "AUXOUT_N16") (pintype "tri_state"))
      (node (ref "U$10") (pin "N6") (pinfunction "GND3_N6") (pintype "power_in"))
      (node (ref "U2") (pin "C2") (pinfunction "VSS_2_C2") (pintype "power_in"))
      (node (ref "U2") (pin "D4") (pinfunction "VSS_3_D4") (pintype "power_in"))
      (node (ref "U2") (pin "D5") (pinfunction "VSS_4_D5") (pintype "power_in"))
      (node (ref "U2") (pin "D6") (pinfunction "VSS_D6") (pintype "power_in"))
      (node (ref "U2") (pin "F1") (pinfunction "VSSA/VREF-_F1") (pintype "power_in"))
    )
    (net (code "11") (name "HIZVT") (class "Default")
      (node (ref "HIZVT") (pin "P$1") (pinfunction "P$1_P$1") (pintype "passive"))
      (node (ref "R80") (pin "1") (pinfunction "1_1") (pintype "passive"))
      (node (ref "R81") (pin "2") (pinfunction "2_2") (pintype "passive"))
      (node (ref "U2") (pin "H6") (pinfunction "PC5_H6") (pintype "bidirectional"))
    )
    (net (code "12") (name "INTAN_CS") (class "Default")
      (node (ref "SPI1") (pin "8") (pinfunction "8_8") (pintype "passive"))
      (node (ref "U2") (pin "H8") (pinfunction "PB12_H8") (pintype "bidirectional"))
    )
    (net (code "13") (name "INTAN_MISO") (class "Default")
      (node (ref "SPI1") (pin "2") (pinfunction "2_2") (pintype "passive"))
      (node (ref "U2") (pin "F2") (pinfunction "PC2_F2") (pintype "bidirectional"))
    )
    (net (code "14") (name "INTAN_MOSI") (class "Default")
      (node (ref "SPI1") (pin "4") (pinfunction "4_4") (pintype "passive"))
      (node (ref "U2") (pin "F7") (pinfunction "PB15_F7") (pintype "bidirectional"))
    )
    (net (code "15") (name "INTAN_SCK") (class "Default")
      (node (ref "SPI1") (pin "6") (pinfunction "6_6") (pintype "passive"))
      (node (ref "U2") (pin "G7") (pinfunction "PB10_G7") (pintype "bidirectional"))
    )
    (net (code "16") (name "LED_B") (class "Default")
      (node (ref "R8") (pin "2") (pinfunction "2_2") (pintype "passive"))
      (node (ref "U2") (pin "A2") (pinfunction "PC13_A2") (pintype "bidirectional"))
    )
    (net (code "17") (name "LED_G") (class "Default")
      (node (ref "R7") (pin "2") (pinfunction "2_2") (pintype "passive"))
      (node (ref "U2") (pin "C5") (pinfunction "PC12_C5") (pintype "bidirectional"))
    )
    (net (code "18") (name "LED_R") (class "Default")
      (node (ref "R9") (pin "2") (pinfunction "2_2") (pintype "passive"))
      (node (ref "U2") (pin "D8") (pinfunction "PC9_D8") (pintype "bidirectional"))
    )
    (net (code "19") (name "Net-(C3-P$2)") (class "Default")
      (node (ref "C3") (pin "2") (pinfunction "P$2_2") (pintype "bidirectional"))
      (node (ref "D1") (pin "1") (pinfunction "CATHODE_1") (pintype "passive"))
      (node (ref "D2") (pin "1") (pinfunction "CATHODE_1") (pintype "passive"))
      (node (ref "K1") (pin "4") (pinfunction "VIN_4") (pintype "bidirectional"))
      (node (ref "R2") (pin "1") (pinfunction "1_1") (pintype "passive"))
    )
    (net (code "20") (name "Net-(C5-P$1)") (class "Default")
      (node (ref "C5") (pin "1") (pinfunction "P$1_1") (pintype "bidirectional"))
      (node (ref "K2") (pin "3") (pinfunction "CAP_3") (pintype "passive"))
    )
    (net (code "21") (name "Net-(C5-P$2)") (class "Default")
      (node (ref "C11") (pin "1") (pinfunction "1_1") (pintype "passive"))
      (node (ref "C5") (pin "2") (pinfunction "P$2_2") (pintype "bidirectional"))
      (node (ref "K2") (pin "4") (pinfunction "VIN_4") (pintype "input"))
      (node (ref "R4") (pin "2") (pinfunction "2_2") (pintype "passive"))
    )
    (net (code "22") (name "Net-(C6-P$1)") (class "Default")
      (node (ref "C6") (pin "1") (pinfunction "P$1_1") (pintype "bidirectional"))
      (node (ref "K2") (pin "6") (pinfunction "VOUT_6") (pintype "output"))
      (node (ref "L1") (pin "P$2") (pinfunction "P$1_P$2") (pintype "bidirectional"))
      (node (ref "R5") (pin "1") (pinfunction "1_1") (pintype "passive"))
    )
    (net (code "23") (name "Net-(C10-P$2)") (class "Default")
      (node (ref "C10") (pin "2") (pinfunction "P$2_2") (pintype "bidirectional"))
      (node (ref "C14") (pin "2") (pinfunction "2_2") (pintype "passive"))
      (node (ref "C18") (pin "2") (pinfunction "P$2_2") (pintype "bidirectional"))
      (node (ref "C48") (pin "1") (pinfunction "P$1_1") (pintype "bidirectional"))
      (node (ref "K15") (pin "11") (pinfunction "EPAD_11") (pintype "passive"))
      (node (ref "K15") (pin "2") (pinfunction "STBY_2") (pintype "input"))
      (node (ref "K15") (pin "9") (pinfunction "D0_9") (pintype "output"))
      (node (ref "K16") (pin "4") (pinfunction "GND_4") (pintype "bidirectional"))
      (node (ref "K17") (pin "3") (pinfunction "GND_3") (pintype "bidirectional"))
      (node (ref "K19") (pin "5") (pinfunction "GND2_5") (pintype "bidirectional"))
      (node (ref "R53") (pin "2") (pinfunction "2_2") (pintype "passive"))
      (node (ref "R56") (pin "1") (pinfunction "1_1") (pintype "passive"))
    )
    (net (code "24") (name "Net-(C13-P$2)") (class "Default")
      (node (ref "C13") (pin "2") (pinfunction "P$2_2") (pintype "bidirectional"))
      (node (ref "C7") (pin "2") (pinfunction "P$2_2") (pintype "bidirectional"))
      (node (ref "C8") (pin "2") (pinfunction "P$2_2") (pintype "bidirectional"))
      (node (ref "C9") (pin "2") (pinfunction "P$2_2") (pintype "bidirectional"))
      (node (ref "MCU") (pin "3") (pinfunction "2_3") (pintype "passive"))
      (node (ref "MCU") (pin "4") (pinfunction "2_4") (pintype "passive"))
      (node (ref "U2") (pin "D2") (pinfunction "VDD_2_D2") (pintype "power_in"))
      (node (ref "U2") (pin "E4") (pinfunction "VDD_3_E4") (pintype "power_in"))
      (node (ref "U2") (pin "E6") (pinfunction "VDD_E6") (pintype "power_in"))
      (node (ref "U2") (pin "H1") (pinfunction "VDDA/VREF+_H1") (pintype "power_in"))
    )
    (net (code "25") (name "Net-(C18-P$1)") (class "Default")
      (node (ref "C18") (pin "1") (pinfunction "P$1_1") (pintype "bidirectional"))
      (node (ref "C47") (pin "1") (pinfunction "P$1_1") (pintype "bidirectional"))
      (node (ref "R57") (pin "1") (pinfunction "1_1") (pintype "passive"))
      (node (ref "U1") (pin "5") (pinfunction "OUT_5") (pintype "output"))
    )
    (net (code "26") (name "Net-(C47-P$2)") (class "Default")
      (node (ref "C47") (pin "2") (pinfunction "P$2_2") (pintype "bidirectional"))
      (node (ref "U1") (pin "3") (pinfunction "BYP_3") (pintype "passive"))
    )
    (net (code "27") (name "Net-(C51-P$2)") (class "Default")
      (node (ref "C51") (pin "2") (pinfunction "P$2_2") (pintype "bidirectional"))
      (node (ref "D10") (pin "2") (pinfunction "ANODE_2") (pintype "passive"))
      (node (ref "U1") (pin "2") (pinfunction "IN_2") (pintype "input"))
      (node (ref "U1") (pin "4") (pinfunction "~{SHDN}_4") (pintype "input"))
    )
    (net (code "28") (name "Net-(C52-P$1)") (class "Default")
      (node (ref "C52") (pin "1") (pinfunction "P$1_1") (pintype "bidirectional"))
      (node (ref "K15") (pin "3") (pinfunction "CAP_3") (pintype "passive"))
    )
    (net (code "29") (name "Net-(C52-P$2)") (class "Default")
      (node (ref "C14") (pin "1") (pinfunction "1_1") (pintype "passive"))
      (node (ref "C52") (pin "2") (pinfunction "P$2_2") (pintype "bidirectional"))
      (node (ref "D9") (pin "1") (pinfunction "CATHODE_1") (pintype "passive"))
      (node (ref "K15") (pin "4") (pinfunction "VIN_4") (pintype "input"))
    )
    (net (code "30") (name "Net-(C57-P$2)") (class "Default")
      (node (ref "C57") (pin "2") (pinfunction "P$2_2") (pintype "bidirectional"))
      (node (ref "C58") (pin "2") (pinfunction "P$2_2") (pintype "bidirectional"))
      (node (ref "INTAN") (pin "3") (pinfunction "2_3") (pintype "passive"))
      (node (ref "INTAN") (pin "4") (pinfunction "2_4") (pintype "passive"))
      (node (ref "U$10") (pin "M15") (pinfunction "VDD1_M15") (pintype "power_in"))
      (node (ref "U$10") (pin "N15") (pinfunction "VDD3_N15") (pintype "power_in"))
      (node (ref "U$10") (pin "N2") (pinfunction "VDD2_N2") (pintype "power_in"))
      (node (ref "U$10") (pin "N3") (pinfunction "AUXIN1_N3") (pintype "input"))
      (node (ref "U$10") (pin "N4") (pinfunction "AUXIN2_N4") (pintype "input"))
      (node (ref "U$10") (pin "N5") (pinfunction "AUXIN3_N5") (pintype "input"))
    )
    (net (code "31") (name "Net-(C60-P$2)") (class "Default")
      (node (ref "C60") (pin "2") (pinfunction "P$2_2") (pintype "bidirectional"))
      (node (ref "U$10") (pin "N17") (pinfunction "ADC_REF_N17") (pintype "passive"))
    )
    (net (code "32") (name "Net-(C62-P$1)") (class "Default")
      (node (ref "C62") (pin "1") (pinfunction "P$1_1") (pintype "bidirectional"))
      (node (ref "U2") (pin "D1") (pinfunction "PH1-OSC_OUT_D1") (pintype "bidirectional"))
      (node (ref "X4") (pin "2") (pinfunction "P$2_2") (pintype "bidirectional"))
    )
    (net (code "33") (name "Net-(C63-P$1)") (class "Default")
      (node (ref "C63") (pin "1") (pinfunction "P$1_1") (pintype "bidirectional"))
      (node (ref "U2") (pin "C1") (pinfunction "PH0-OSC_IN_C1") (pintype "bidirectional"))
      (node (ref "X4") (pin "1") (pinfunction "P$1_1") (pintype "bidirectional"))
    )
    (net (code "34") (name "Net-(C64-P$1)") (class "Default")
      (node (ref "C64") (pin "1") (pinfunction "P$1_1") (pintype "bidirectional"))
      (node (ref "U2") (pin "B1") (pinfunction "PC15-OSC32_OUT_B1") (pintype "bidirectional"))
      (node (ref "X3") (pin "2") (pinfunction "P$2_2") (pintype "bidirectional"))
    )
    (net (code "35") (name "Net-(C65-P$1)") (class "Default")
      (node (ref "C65") (pin "1") (pinfunction "P$1_1") (pintype "bidirectional"))
      (node (ref "U2") (pin "A1") (pinfunction "PC14-OSC32_IN_A1") (pintype "bidirectional"))
      (node (ref "X3") (pin "1") (pinfunction "P$1_1") (pintype "bidirectional"))
    )
    (net (code "36") (name "Net-(D8-ANODE)") (class "Default")
      (node (ref "D8") (pin "2") (pinfunction "ANODE_2") (pintype "passive"))
      (node (ref "JP4") (pin "3") (pinfunction "2_3") (pintype "passive"))
      (node (ref "JP4") (pin "4") (pinfunction "2_4") (pintype "passive"))
    )
    (net (code "37") (name "Net-(K2-D1)") (class "Default")
      (node (ref "C12") (pin "2") (pinfunction "2_2") (pintype "passive"))
      (node (ref "K2") (pin "7") (pinfunction "VIN2_7") (pintype "input"))
      (node (ref "K2") (pin "8") (pinfunction "D1_8") (pintype "output"))
    )
    (net (code "38") (name "Net-(K2-SW)") (class "Default")
      (node (ref "K2") (pin "5") (pinfunction "SW_5") (pintype "passive"))
      (node (ref "L1") (pin "P$1") (pinfunction "P$2_P$1") (pintype "bidirectional"))
    )
    (net (code "39") (name "Net-(K15-SW)") (class "Default")
      (node (ref "K15") (pin "5") (pinfunction "SW_5") (pintype "passive"))
      (node (ref "L3") (pin "1") (pinfunction "P$2_1") (pintype "bidirectional"))
    )
    (net (code "40") (name "Net-(K16-OUT1)") (class "Default")
      (node (ref "K16") (pin "1") (pinfunction "OUT1_1") (pintype "bidirectional"))
      (node (ref "K17") (pin "1") (pinfunction "A_1") (pintype "bidirectional"))
    )
    (net (code "41") (name "Net-(K16-OUT2)") (class "Default")
      (node (ref "K16") (pin "7") (pinfunction "OUT2_7") (pintype "bidirectional"))
      (node (ref "K17") (pin "2") (pinfunction "B_2") (pintype "bidirectional"))
    )
    (net (code "42") (name "Net-(K18-CLK)") (class "Default")
      (node (ref "K18") (pin "1") (pinfunction "CLK_1") (pintype "input"))
      (node (ref "K20") (pin "5") (pinfunction "TAP_5_5") (pintype "output"))
    )
    (net (code "43") (name "Net-(K23-SENSE)") (class "Default")
      (node (ref "K23") (pin "5") (pinfunction "SENSE_5") (pintype "passive"))
      (node (ref "R65") (pin "2") (pinfunction "2_2") (pintype "passive"))
      (node (ref "R66") (pin "1") (pinfunction "1_1") (pintype "passive"))
    )
    (net (code "44") (name "Net-(K23-~{RESET})") (class "Default")
      (node (ref "K23") (pin "3") (pinfunction "~{RESET}_3") (pintype "passive"))
      (node (ref "R67") (pin "2") (pinfunction "2_2") (pintype "passive"))
    )
    (net (code "45") (name "Net-(K27-1A)") (class "Default")
      (node (ref "DELC1") (pin "3") (pinfunction "3_3") (pintype "passive"))
      (node (ref "K27") (pin "1") (pinfunction "1A_1") (pintype "input"))
      (node (ref "K27") (pin "2") (pinfunction "3Y_2") (pintype "output"))
    )
    (net (code "46") (name "Net-(K27-1Y)") (class "Default")
      (node (ref "DELC1") (pin "1") (pinfunction "1_1") (pintype "passive"))
      (node (ref "K27") (pin "7") (pinfunction "1Y_7") (pintype "output"))
    )
    (net (code "47") (name "Net-(K27-2A)") (class "Default")
      (node (ref "DELC1") (pin "7") (pinfunction "7_7") (pintype "passive"))
      (node (ref "K27") (pin "3") (pinfunction "2A_3") (pintype "input"))
      (node (ref "K28") (pin "2") (pinfunction "CLK_2") (pintype "input"))
      (node (ref "SPI1") (pin "7") (pinfunction "7_7") (pintype "passive"))
    )
    (net (code "48") (name "Net-(K27-2Y)") (class "Default")
      (node (ref "DELC1") (pin "5") (pinfunction "5_5") (pintype "passive"))
      (node (ref "K27") (pin "5") (pinfunction "2Y_5") (pintype "output"))
      (node (ref "K27") (pin "6") (pinfunction "3A_6") (pintype "input"))
    )
    (net (code "49") (name "Net-(K28-D)") (class "Default")
      (node (ref "K28") (pin "1") (pinfunction "D_1") (pintype "input"))
      (node (ref "K28") (pin "4") (pinfunction "Q_4") (pintype "output"))
      (node (ref "K29") (pin "2") (pinfunction "B_2") (pintype "passive"))
    )
    (net (code "50") (name "Net-(K29-A)") (class "Default")
      (node (ref "DELC1") (pin "2") (pinfunction "2_2") (pintype "passive"))
      (node (ref "DELC1") (pin "4") (pinfunction "4_4") (pintype "passive"))
      (node (ref "DELC1") (pin "6") (pinfunction "6_6") (pintype "passive"))
      (node (ref "DELC1") (pin "8") (pinfunction "8_8") (pintype "passive"))
      (node (ref "K29") (pin "1") (pinfunction "A_1") (pintype "passive"))
    )
    (net (code "51") (name "Net-(K29-Y)") (class "Default")
      (node (ref "K29") (pin "4") (pinfunction "Y_4") (pintype "passive"))
      (node (ref "SPI_CS+") (pin "2") (pinfunction "2_2") (pintype "passive"))
    )
    (net (code "52") (name "Net-(PWR-2-Pad3)") (class "Default")
      (node (ref "PWR") (pin "3") (pinfunction "2_3") (pintype "passive"))
      (node (ref "PWR") (pin "4") (pinfunction "2_4") (pintype "passive"))
      (node (ref "R5") (pin "2") (pinfunction "2_2") (pintype "passive"))
    )
    (net (code "53") (name "Net-(Q2-BASE)") (class "Default")
      (node (ref "Q2") (pin "2") (pinfunction "BASE_2") (pintype "passive"))
      (node (ref "R50") (pin "1") (pinfunction "1_1") (pintype "passive"))
      (node (ref "R51") (pin "2") (pinfunction "2_2") (pintype "passive"))
    )
    (net (code "54") (name "Net-(Q2-COLLECTOR)") (class "Default")
      (node (ref "JP4") (pin "1") (pinfunction "1_1") (pintype "passive"))
      (node (ref "JP4") (pin "2") (pinfunction "1_2") (pintype "passive"))
      (node (ref "Q2") (pin "1") (pinfunction "COLLECTOR_1") (pintype "passive"))
    )
    (net (code "55") (name "Net-(Q2-EMITTER)") (class "Default")
      (node (ref "Q2") (pin "3") (pinfunction "EMITTER_3") (pintype "passive"))
      (node (ref "R49") (pin "1") (pinfunction "1_1") (pintype "passive"))
    )
    (net (code "56") (name "Net-(R7-Pad1)") (class "Default")
      (node (ref "R7") (pin "1") (pinfunction "1_1") (pintype "passive"))
      (node (ref "U$6") (pin "B") (pinfunction "B_B") (pintype "passive"))
    )
    (net (code "57") (name "Net-(R8-Pad1)") (class "Default")
      (node (ref "R8") (pin "1") (pinfunction "1_1") (pintype "passive"))
      (node (ref "U$6") (pin "G") (pinfunction "G_G") (pintype "passive"))
    )
    (net (code "58") (name "Net-(R9-Pad1)") (class "Default")
      (node (ref "R9") (pin "1") (pinfunction "1_1") (pintype "passive"))
      (node (ref "U$6") (pin "R") (pinfunction "R_R") (pintype "passive"))
    )
    (net (code "59") (name "Net-(U$10-IN0)") (class "Default")
      (node (ref "IN1") (pin "P$1") (pinfunction "P$1_P$1") (pintype "passive"))
      (node (ref "U$10") (pin "K2") (pinfunction "IN0_K2") (pintype "input"))
      (node (ref "U$4") (pin "P$32") (pinfunction "P$32_P$32") (pintype "bidirectional"))
    )
    (net (code "60") (name "Net-(U$10-IN1)") (class "Default")
      (node (ref "U$10") (pin "J1") (pinfunction "IN1_J1") (pintype "input"))
      (node (ref "U$4") (pin "P$31") (pinfunction "P$31_P$31") (pintype "bidirectional"))
    )
    (net (code "61") (name "Net-(U$10-IN2)") (class "Default")
      (node (ref "U$10") (pin "J2") (pinfunction "IN2_J2") (pintype "input"))
      (node (ref "U$4") (pin "P$30") (pinfunction "P$30_P$30") (pintype "bidirectional"))
    )
    (net (code "62") (name "Net-(U$10-IN3)") (class "Default")
      (node (ref "U$10") (pin "H1") (pinfunction "IN3_H1") (pintype "input"))
      (node (ref "U$4") (pin "P$29") (pinfunction "P$29_P$29") (pintype "bidirectional"))
    )
    (net (code "63") (name "Net-(U$10-IN4)") (class "Default")
      (node (ref "U$10") (pin "H2") (pinfunction "IN4_H2") (pintype "input"))
      (node (ref "U$4") (pin "P$28") (pinfunction "P$28_P$28") (pintype "bidirectional"))
    )
    (net (code "64") (name "Net-(U$10-IN5)") (class "Default")
      (node (ref "U$10") (pin "G1") (pinfunction "IN5_G1") (pintype "input"))
      (node (ref "U$4") (pin "P$27") (pinfunction "P$27_P$27") (pintype "bidirectional"))
    )
    (net (code "65") (name "Net-(U$10-IN6)") (class "Default")
      (node (ref "U$10") (pin "G2") (pinfunction "IN6_G2") (pintype "input"))
      (node (ref "U$4") (pin "P$26") (pinfunction "P$26_P$26") (pintype "bidirectional"))
    )
    (net (code "66") (name "Net-(U$10-IN7)") (class "Default")
      (node (ref "U$10") (pin "F1") (pinfunction "IN7_F1") (pintype "input"))
      (node (ref "U$4") (pin "P$25") (pinfunction "P$25_P$25") (pintype "bidirectional"))
    )
    (net (code "67") (name "Net-(U$10-IN8)") (class "Default")
      (node (ref "U$10") (pin "F2") (pinfunction "IN8_F2") (pintype "input"))
      (node (ref "U$4") (pin "P$24") (pinfunction "P$24_P$24") (pintype "bidirectional"))
    )
    (net (code "68") (name "Net-(U$10-IN9)") (class "Default")
      (node (ref "U$10") (pin "E1") (pinfunction "IN9_E1") (pintype "input"))
      (node (ref "U$4") (pin "P$23") (pinfunction "P$23_P$23") (pintype "bidirectional"))
    )
    (net (code "69") (name "Net-(U$10-IN10)") (class "Default")
      (node (ref "U$10") (pin "E2") (pinfunction "IN10_E2") (pintype "input"))
      (node (ref "U$4") (pin "P$22") (pinfunction "P$22_P$22") (pintype "bidirectional"))
    )
    (net (code "70") (name "Net-(U$10-IN11)") (class "Default")
      (node (ref "U$10") (pin "D1") (pinfunction "IN11_D1") (pintype "input"))
      (node (ref "U$4") (pin "P$21") (pinfunction "P$21_P$21") (pintype "bidirectional"))
    )
    (net (code "71") (name "Net-(U$10-IN12)") (class "Default")
      (node (ref "U$10") (pin "D2") (pinfunction "IN12_D2") (pintype "input"))
      (node (ref "U$4") (pin "P$20") (pinfunction "P$20_P$20") (pintype "bidirectional"))
    )
    (net (code "72") (name "Net-(U$10-IN13)") (class "Default")
      (node (ref "U$10") (pin "C1") (pinfunction "IN13_C1") (pintype "input"))
      (node (ref "U$4") (pin "P$19") (pinfunction "P$19_P$19") (pintype "bidirectional"))
    )
    (net (code "73") (name "Net-(U$10-IN14)") (class "Default")
      (node (ref "U$10") (pin "C2") (pinfunction "IN14_C2") (pintype "input"))
      (node (ref "U$4") (pin "P$18") (pinfunction "P$18_P$18") (pintype "bidirectional"))
    )
    (net (code "74") (name "Net-(U$10-IN15)") (class "Default")
      (node (ref "U$10") (pin "B1") (pinfunction "IN15_B1") (pintype "input"))
      (node (ref "U$4") (pin "P$17") (pinfunction "P$17_P$17") (pintype "bidirectional"))
    )
    (net (code "75") (name "Net-(U$10-IN16)") (class "Default")
      (node (ref "U$10") (pin "A1") (pinfunction "IN16_A1") (pintype "input"))
      (node (ref "U$4") (pin "P$16") (pinfunction "P$16_P$16") (pintype "bidirectional"))
    )
    (net (code "76") (name "Net-(U$10-IN17)") (class "Default")
      (node (ref "U$10") (pin "B2") (pinfunction "IN17_B2") (pintype "input"))
      (node (ref "U$4") (pin "P$15") (pinfunction "P$15_P$15") (pintype "bidirectional"))
    )
    (net (code "77") (name "Net-(U$10-IN18)") (class "Default")
      (node (ref "U$10") (pin "A2") (pinfunction "IN18_A2") (pintype "input"))
      (node (ref "U$4") (pin "P$14") (pinfunction "P$14_P$14") (pintype "bidirectional"))
    )
    (net (code "78") (name "Net-(U$10-IN19)") (class "Default")
      (node (ref "U$10") (pin "B3") (pinfunction "IN19_B3") (pintype "input"))
      (node (ref "U$4") (pin "P$13") (pinfunction "P$13_P$13") (pintype "bidirectional"))
    )
    (net (code "79") (name "Net-(U$10-IN20)") (class "Default")
      (node (ref "U$10") (pin "A3") (pinfunction "IN20_A3") (pintype "input"))
      (node (ref "U$4") (pin "P$12") (pinfunction "P$12_P$12") (pintype "bidirectional"))
    )
    (net (code "80") (name "Net-(U$10-IN21)") (class "Default")
      (node (ref "U$10") (pin "B4") (pinfunction "IN21_B4") (pintype "input"))
      (node (ref "U$4") (pin "P$11") (pinfunction "P$11_P$11") (pintype "bidirectional"))
    )
    (net (code "81") (name "Net-(U$10-IN22)") (class "Default")
      (node (ref "U$10") (pin "A4") (pinfunction "IN22_A4") (pintype "input"))
      (node (ref "U$4") (pin "P$10") (pinfunction "P$10_P$10") (pintype "bidirectional"))
    )
    (net (code "82") (name "Net-(U$10-IN23)") (class "Default")
      (node (ref "U$10") (pin "B5") (pinfunction "IN23_B5") (pintype "input"))
      (node (ref "U$4") (pin "P$9") (pinfunction "P$9_P$9") (pintype "bidirectional"))
    )
    (net (code "83") (name "Net-(U$10-IN24)") (class "Default")
      (node (ref "U$10") (pin "A5") (pinfunction "IN24_A5") (pintype "input"))
      (node (ref "U$4") (pin "P$8") (pinfunction "P$8_P$8") (pintype "bidirectional"))
    )
    (net (code "84") (name "Net-(U$10-IN25)") (class "Default")
      (node (ref "U$10") (pin "B6") (pinfunction "IN25_B6") (pintype "input"))
      (node (ref "U$4") (pin "P$7") (pinfunction "P$7_P$7") (pintype "bidirectional"))
    )
    (net (code "85") (name "Net-(U$10-IN26)") (class "Default")
      (node (ref "U$10") (pin "A6") (pinfunction "IN26_A6") (pintype "input"))
      (node (ref "U$4") (pin "P$6") (pinfunction "P$6_P$6") (pintype "bidirectional"))
    )
    (net (code "86") (name "Net-(U$10-IN27)") (class "Default")
      (node (ref "U$10") (pin "B7") (pinfunction "IN27_B7") (pintype "input"))
      (node (ref "U$4") (pin "P$5") (pinfunction "P$5_P$5") (pintype "bidirectional"))
    )
    (net (code "87") (name "Net-(U$10-IN28)") (class "Default")
      (node (ref "U$10") (pin "A7") (pinfunction "IN28_A7") (pintype "input"))
      (node (ref "U$4") (pin "P$4") (pinfunction "P$4_P$4") (pintype "bidirectional"))
    )
    (net (code "88") (name "Net-(U$10-IN29)") (class "Default")
      (node (ref "U$10") (pin "B8") (pinfunction "IN29_B8") (pintype "input"))
      (node (ref "U$4") (pin "P$3") (pinfunction "P$3_P$3") (pintype "bidirectional"))
    )
    (net (code "89") (name "Net-(U$10-IN30)") (class "Default")
      (node (ref "U$10") (pin "A8") (pinfunction "IN30_A8") (pintype "input"))
      (node (ref "U$4") (pin "P$2") (pinfunction "P$2_P$2") (pintype "bidirectional"))
    )
    (net (code "90") (name "Net-(U$10-IN31)") (class "Default")
      (node (ref "U$10") (pin "B9") (pinfunction "IN31_B9") (pintype "input"))
      (node (ref "U$4") (pin "P$1") (pinfunction "P$1_P$1") (pintype "bidirectional"))
    )
    (net (code "91") (name "Net-(U$10-IN32)") (class "Default")
      (node (ref "U$10") (pin "A9") (pinfunction "IN32_A9") (pintype "input"))
      (node (ref "U$3") (pin "P$32") (pinfunction "P$32_P$32") (pintype "bidirectional"))
    )
    (net (code "92") (name "Net-(U$10-IN33)") (class "Default")
      (node (ref "U$10") (pin "A10") (pinfunction "IN33_A10") (pintype "input"))
      (node (ref "U$3") (pin "P$31") (pinfunction "P$31_P$31") (pintype "bidirectional"))
    )
    (net (code "93") (name "Net-(U$10-IN34)") (class "Default")
      (node (ref "U$10") (pin "B10") (pinfunction "IN34_B10") (pintype "input"))
      (node (ref "U$3") (pin "P$30") (pinfunction "P$30_P$30") (pintype "bidirectional"))
    )
    (net (code "94") (name "Net-(U$10-IN35)") (class "Default")
      (node (ref "U$10") (pin "A11") (pinfunction "IN35_A11") (pintype "input"))
      (node (ref "U$3") (pin "P$29") (pinfunction "P$29_P$29") (pintype "bidirectional"))
    )
    (net (code "95") (name "Net-(U$10-IN36)") (class "Default")
      (node (ref "U$10") (pin "B11") (pinfunction "IN36_B11") (pintype "input"))
      (node (ref "U$3") (pin "P$28") (pinfunction "P$28_P$28") (pintype "bidirectional"))
    )
    (net (code "96") (name "Net-(U$10-IN37)") (class "Default")
      (node (ref "U$10") (pin "A12") (pinfunction "IN37_A12") (pintype "input"))
      (node (ref "U$3") (pin "P$27") (pinfunction "P$27_P$27") (pintype "bidirectional"))
    )
    (net (code "97") (name "Net-(U$10-IN38)") (class "Default")
      (node (ref "U$10") (pin "B12") (pinfunction "IN38_B12") (pintype "input"))
      (node (ref "U$3") (pin "P$26") (pinfunction "P$26_P$26") (pintype "bidirectional"))
    )
    (net (code "98") (name "Net-(U$10-IN39)") (class "Default")
      (node (ref "U$10") (pin "A13") (pinfunction "IN39_A13") (pintype "input"))
      (node (ref "U$3") (pin "P$25") (pinfunction "P$25_P$25") (pintype "bidirectional"))
    )
    (net (code "99") (name "Net-(U$10-IN40)") (class "Default")
      (node (ref "U$10") (pin "B13") (pinfunction "IN40_B13") (pintype "input"))
      (node (ref "U$3") (pin "P$24") (pinfunction "P$24_P$24") (pintype "bidirectional"))
    )
    (net (code "100") (name "Net-(U$10-IN41)") (class "Default")
      (node (ref "U$10") (pin "A14") (pinfunction "IN41_A14") (pintype "input"))
      (node (ref "U$3") (pin "P$23") (pinfunction "P$23_P$23") (pintype "bidirectional"))
    )
    (net (code "101") (name "Net-(U$10-IN42)") (class "Default")
      (node (ref "U$10") (pin "B14") (pinfunction "IN42_B14") (pintype "input"))
      (node (ref "U$3") (pin "P$22") (pinfunction "P$22_P$22") (pintype "bidirectional"))
    )
    (net (code "102") (name "Net-(U$10-IN43)") (class "Default")
      (node (ref "U$10") (pin "A15") (pinfunction "IN43_A15") (pintype "input"))
      (node (ref "U$3") (pin "P$21") (pinfunction "P$21_P$21") (pintype "bidirectional"))
    )
    (net (code "103") (name "Net-(U$10-IN44)") (class "Default")
      (node (ref "U$10") (pin "B15") (pinfunction "IN44_B15") (pintype "input"))
      (node (ref "U$3") (pin "P$20") (pinfunction "P$20_P$20") (pintype "bidirectional"))
    )
    (net (code "104") (name "Net-(U$10-IN45)") (class "Default")
      (node (ref "U$10") (pin "A16") (pinfunction "IN45_A16") (pintype "input"))
      (node (ref "U$3") (pin "P$19") (pinfunction "P$19_P$19") (pintype "bidirectional"))
    )
    (net (code "105") (name "Net-(U$10-IN46)") (class "Default")
      (node (ref "U$10") (pin "B16") (pinfunction "IN46_B16") (pintype "input"))
      (node (ref "U$3") (pin "P$18") (pinfunction "P$18_P$18") (pintype "bidirectional"))
    )
    (net (code "106") (name "Net-(U$10-IN47)") (class "Default")
      (node (ref "U$10") (pin "A17") (pinfunction "IN47_A17") (pintype "input"))
      (node (ref "U$3") (pin "P$17") (pinfunction "P$17_P$17") (pintype "bidirectional"))
    )
    (net (code "107") (name "Net-(U$10-IN48)") (class "Default")
      (node (ref "U$10") (pin "B17") (pinfunction "IN48_B17") (pintype "input"))
      (node (ref "U$3") (pin "P$16") (pinfunction "P$16_P$16") (pintype "bidirectional"))
    )
    (net (code "108") (name "Net-(U$10-IN49)") (class "Default")
      (node (ref "U$10") (pin "C16") (pinfunction "IN49_C16") (pintype "input"))
      (node (ref "U$3") (pin "P$15") (pinfunction "P$15_P$15") (pintype "bidirectional"))
    )
    (net (code "109") (name "Net-(U$10-IN50)") (class "Default")
      (node (ref "U$10") (pin "C17") (pinfunction "IN50_C17") (pintype "input"))
      (node (ref "U$3") (pin "P$14") (pinfunction "P$14_P$14") (pintype "bidirectional"))
    )
    (net (code "110") (name "Net-(U$10-IN51)") (class "Default")
      (node (ref "U$10") (pin "D16") (pinfunction "IN51_D16") (pintype "input"))
      (node (ref "U$3") (pin "P$13") (pinfunction "P$13_P$13") (pintype "bidirectional"))
    )
    (net (code "111") (name "Net-(U$10-IN52)") (class "Default")
      (node (ref "U$10") (pin "D17") (pinfunction "IN52_D17") (pintype "input"))
      (node (ref "U$3") (pin "P$12") (pinfunction "P$12_P$12") (pintype "bidirectional"))
    )
    (net (code "112") (name "Net-(U$10-IN53)") (class "Default")
      (node (ref "U$10") (pin "E16") (pinfunction "IN53_E16") (pintype "input"))
      (node (ref "U$3") (pin "P$11") (pinfunction "P$11_P$11") (pintype "bidirectional"))
    )
    (net (code "113") (name "Net-(U$10-IN54)") (class "Default")
      (node (ref "U$10") (pin "E17") (pinfunction "IN54_E17") (pintype "input"))
      (node (ref "U$3") (pin "P$10") (pinfunction "P$10_P$10") (pintype "bidirectional"))
    )
    (net (code "114") (name "Net-(U$10-IN55)") (class "Default")
      (node (ref "U$10") (pin "F16") (pinfunction "IN55_F16") (pintype "input"))
      (node (ref "U$3") (pin "P$9") (pinfunction "P$9_P$9") (pintype "bidirectional"))
    )
    (net (code "115") (name "Net-(U$10-IN56)") (class "Default")
      (node (ref "U$10") (pin "F17") (pinfunction "IN56_F17") (pintype "input"))
      (node (ref "U$3") (pin "P$8") (pinfunction "P$8_P$8") (pintype "bidirectional"))
    )
    (net (code "116") (name "Net-(U$10-IN57)") (class "Default")
      (node (ref "U$10") (pin "G16") (pinfunction "IN57_G16") (pintype "input"))
      (node (ref "U$3") (pin "P$7") (pinfunction "P$7_P$7") (pintype "bidirectional"))
    )
    (net (code "117") (name "Net-(U$10-IN58)") (class "Default")
      (node (ref "U$10") (pin "G17") (pinfunction "IN58_G17") (pintype "input"))
      (node (ref "U$3") (pin "P$6") (pinfunction "P$6_P$6") (pintype "bidirectional"))
    )
    (net (code "118") (name "Net-(U$10-IN59)") (class "Default")
      (node (ref "U$10") (pin "H16") (pinfunction "IN59_H16") (pintype "input"))
      (node (ref "U$3") (pin "P$5") (pinfunction "P$5_P$5") (pintype "bidirectional"))
    )
    (net (code "119") (name "Net-(U$10-IN60)") (class "Default")
      (node (ref "U$10") (pin "H17") (pinfunction "IN60_H17") (pintype "input"))
      (node (ref "U$3") (pin "P$4") (pinfunction "P$4_P$4") (pintype "bidirectional"))
    )
    (net (code "120") (name "Net-(U$10-IN61)") (class "Default")
      (node (ref "U$10") (pin "J16") (pinfunction "IN61_J16") (pintype "input"))
      (node (ref "U$3") (pin "P$3") (pinfunction "P$3_P$3") (pintype "bidirectional"))
    )
    (net (code "121") (name "Net-(U$10-IN62)") (class "Default")
      (node (ref "U$10") (pin "J17") (pinfunction "IN62_J17") (pintype "input"))
      (node (ref "U$3") (pin "P$2") (pinfunction "P$2_P$2") (pintype "bidirectional"))
    )
    (net (code "122") (name "Net-(U$10-IN63)") (class "Default")
      (node (ref "U$10") (pin "K16") (pinfunction "IN63_K16") (pintype "input"))
      (node (ref "U$3") (pin "P$1") (pinfunction "P$1_P$1") (pintype "bidirectional"))
    )
    (net (code "123") (name "Net-(U$10-MISO+)") (class "Default")
      (node (ref "SPI1") (pin "1") (pinfunction "1_1") (pintype "passive"))
      (node (ref "U$10") (pin "N14") (pinfunction "MISO+_N14") (pintype "output"))
    )
    (net (code "124") (name "Net-(U$10-MOSI+)") (class "Default")
      (node (ref "SPI1") (pin "3") (pinfunction "3_3") (pintype "passive"))
      (node (ref "U$10") (pin "N12") (pinfunction "MOSI+_N12") (pintype "input"))
    )
    (net (code "125") (name "Net-(U$10-REF_ELEC)") (class "Default")
      (node (ref "REF1") (pin "2") (pinfunction "2_2") (pintype "passive"))
      (node (ref "U$10") (pin "M1") (pinfunction "REF_ELEC_M1") (pintype "input"))
    )
    (net (code "126") (name "Net-(U$10-SCLK+)") (class "Default")
      (node (ref "SPI1") (pin "5") (pinfunction "5_5") (pintype "passive"))
      (node (ref "U$10") (pin "N10") (pinfunction "SCLK+_N10") (pintype "input"))
    )
    (net (code "127") (name "Net-(U$10-~{CS}+)") (class "Default")
      (node (ref "SPI_CS+") (pin "1") (pinfunction "1_1") (pintype "passive"))
      (node (ref "U$10") (pin "N8") (pinfunction "~{CS}+_N8") (pintype "input"))
    )
    (net (code "128") (name "Net-(U2A-NRST)") (class "Default")
      (node (ref "R67") (pin "1") (pinfunction "1_1") (pintype "passive"))
      (node (ref "U2") (pin "E1") (pinfunction "NRST_E1") (pintype "bidirectional"))
    )
    (net (code "129") (name "Net-(U2A-PA11)") (class "Default")
      (node (ref "R11") (pin "1") (pinfunction "1_1") (pintype "passive"))
      (node (ref "U2") (pin "C8") (pinfunction "PA11_C8") (pintype "bidirectional"))
      (node (ref "USB1") (pin "1") (pinfunction "1_1") (pintype "passive"))
    )
    (net (code "130") (name "Net-(U2A-PA12)") (class "Default")
      (node (ref "R10") (pin "1") (pinfunction "1_1") (pintype "passive"))
      (node (ref "U2") (pin "B8") (pinfunction "PA12_B8") (pintype "bidirectional"))
      (node (ref "USB1") (pin "2") (pinfunction "2_2") (pintype "passive"))
    )
    (net (code "131") (name "Net-(U2A-PA13)") (class "Default")
      (node (ref "JTAG1") (pin "5") (pinfunction "5_5") (pintype "bidirectional"))
      (node (ref "U2") (pin "A8") (pinfunction "PA13_A8") (pintype "bidirectional"))
    )
    (net (code "132") (name "Net-(U2A-PA14)") (class "Default")
      (node (ref "JTAG1") (pin "1") (pinfunction "1_1") (pintype "bidirectional"))
      (node (ref "U2") (pin "A7") (pinfunction "PA14_A7") (pintype "bidirectional"))
    )
    (net (code "133") (name "Net-(U2A-PA15)") (class "Default")
      (node (ref "JTAG1") (pin "9") (pinfunction "9_9") (pintype "bidirectional"))
      (node (ref "U2") (pin "A6") (pinfunction "PA15_A6") (pintype "bidirectional"))
    )
    (net (code "134") (name "Net-(U2A-PB3)") (class "Default")
      (node (ref "JTAG1") (pin "3") (pinfunction "3_3") (pintype "bidirectional"))
      (node (ref "U2") (pin "A5") (pinfunction "PB3_A5") (pintype "bidirectional"))
    )
    (net (code "135") (name "Net-(U2A-PB4)") (class "Default")
      (node (ref "JTAG1") (pin "8") (pinfunction "8_8") (pintype "bidirectional"))
      (node (ref "U2") (pin "A4") (pinfunction "PB4_A4") (pintype "bidirectional"))
    )
    (net (code "136") (name "Net-(U2A-PB13)") (class "Default")
      (node (ref "GPIO") (pin "2") (pinfunction "2_2") (pintype "passive"))
      (node (ref "U2") (pin "G8") (pinfunction "PB13_G8") (pintype "bidirectional"))
    )
    (net (code "137") (name "Net-(U2A-PB14)") (class "Default")
      (node (ref "GPIO") (pin "1") (pinfunction "1_1") (pintype "passive"))
      (node (ref "U2") (pin "F8") (pinfunction "PB14_F8") (pintype "bidirectional"))
    )
    (net (code "138") (name "Net-(U2B-VDDUSB)") (class "Default")
      (node (ref "R6") (pin "1") (pinfunction "1_1") (pintype "passive"))
      (node (ref "U2") (pin "E5") (pinfunction "VDDUSB_E5") (pintype "power_in"))
      (node (ref "USB1") (pin "3") (pinfunction "3_3") (pintype "passive"))
    )
    (net (code "139") (name "RXCAN") (class "Default")
      (node (ref "K18") (pin "4") (pinfunction "Q_4") (pintype "output"))
      (node (ref "RXCAN") (pin "P$1") (pinfunction "P$1_P$1") (pintype "passive"))
      (node (ref "U2") (pin "B3") (pinfunction "PB8_B3") (pintype "bidirectional"))
    )
    (net (code "140") (name "RXUART") (class "Default")
      (node (ref "U2") (pin "B7") (pinfunction "PC10_B7") (pintype "bidirectional"))
      (node (ref "UART") (pin "1") (pinfunction "1_1") (pintype "passive"))
    )
    (net (code "141") (name "TXCAN") (class "Default")
      (node (ref "K19") (pin "2") (pinfunction "IN1_2") (pintype "bidirectional"))
      (node (ref "R58") (pin "1") (pinfunction "1_1") (pintype "passive"))
      (node (ref "TXCAN") (pin "P$1") (pinfunction "P$1_P$1") (pintype "passive"))
      (node (ref "U2") (pin "A3") (pinfunction "PB9_A3") (pintype "bidirectional"))
    )
    (net (code "142") (name "TXCANBUS") (class "Default")
      (node (ref "K19") (pin "7") (pinfunction "OUT1_7") (pintype "bidirectional"))
      (node (ref "R51") (pin "1") (pinfunction "1_1") (pintype "passive"))
    )
    (net (code "143") (name "TXUART") (class "Default")
      (node (ref "U2") (pin "B6") (pinfunction "PC11_B6") (pintype "bidirectional"))
      (node (ref "UART") (pin "2") (pinfunction "2_2") (pintype "passive"))
    )
    (net (code "144") (name "VABD") (class "Default")
      (node (ref "C46") (pin "1") (pinfunction "P$1_1") (pintype "bidirectional"))
      (node (ref "K16") (pin "3") (pinfunction "+IN1_3") (pintype "bidirectional"))
      (node (ref "K16") (pin "6") (pinfunction "-IN2_6") (pintype "bidirectional"))
      (node (ref "R47") (pin "1") (pinfunction "1_1") (pintype "passive"))
      (node (ref "R48") (pin "2") (pinfunction "2_2") (pintype "passive"))
    )
    (net (code "145") (name "VBAT") (class "Default")
      (node (ref "U2") (pin "B2") (pinfunction "VBAT_B2") (pintype "power_in"))
    )
    (net (code "146") (name "VCC") (class "Default")
      (node (ref "K29") (pin "6") (pinfunction "VCC_6") (pintype "power_in"))
    )
    (net (code "147") (name "VIC") (class "Default")
      (node (ref "K1") (pin "3") (pinfunction "IOUT_3") (pintype "bidirectional"))
      (node (ref "R3") (pin "2") (pinfunction "2_2") (pintype "passive"))
      (node (ref "R85") (pin "1") (pinfunction "1_1") (pintype "passive"))
      (node (ref "VIC") (pin "P$1") (pinfunction "P$1_P$1") (pintype "passive"))
    )
    (net (code "148") (name "VICAIN") (class "Default")
      (node (ref "C82") (pin "2") (pinfunction "P$2_2") (pintype "bidirectional"))
      (node (ref "R85") (pin "2") (pinfunction "2_2") (pintype "passive"))
      (node (ref "U2") (pin "H3") (pinfunction "PA4_H3") (pintype "bidirectional"))
      (node (ref "VICAIN") (pin "P$1") (pinfunction "P$1_P$1") (pintype "passive"))
    )
    (net (code "149") (name "VIN") (class "Default")
      (node (ref "C4") (pin "2") (pinfunction "P$2_2") (pintype "bidirectional"))
      (node (ref "K1") (pin "5") (pinfunction "LOAD_5") (pintype "bidirectional"))
      (node (ref "R2") (pin "2") (pinfunction "2_2") (pintype "passive"))
      (node (ref "R4") (pin "1") (pinfunction "1_1") (pintype "passive"))
      (node (ref "R84") (pin "1") (pinfunction "1_1") (pintype "passive"))
      (node (ref "VIN") (pin "P$1") (pinfunction "P$1_P$1") (pintype "passive"))
    )
    (net (code "150") (name "VIN2") (class "Default")
      (node (ref "C10") (pin "1") (pinfunction "P$1_1") (pintype "bidirectional"))
      (node (ref "K15") (pin "1") (pinfunction "EN_1") (pintype "input"))
      (node (ref "K15") (pin "7") (pinfunction "VIN2_7") (pintype "input"))
      (node (ref "K15") (pin "8") (pinfunction "D1_8") (pintype "output"))
      (node (ref "K2") (pin "1") (pinfunction "EN_1") (pintype "input"))
    )
    (net (code "151") (name "VINAIN") (class "Default")
      (node (ref "C83") (pin "2") (pinfunction "P$2_2") (pintype "bidirectional"))
      (node (ref "R84") (pin "2") (pinfunction "2_2") (pintype "passive"))
      (node (ref "R86") (pin "2") (pinfunction "2_2") (pintype "passive"))
      (node (ref "U2") (pin "H4") (pinfunction "PA7_H4") (pintype "bidirectional"))
      (node (ref "VINAIN") (pin "P$1") (pinfunction "P$1_P$1") (pintype "passive"))
    )
    (net (code "152") (name "VTN") (class "Default")
      (node (ref "K16") (pin "5") (pinfunction "+IN2_5") (pintype "bidirectional"))
      (node (ref "R56") (pin "2") (pinfunction "2_2") (pintype "passive"))
      (node (ref "R57") (pin "2") (pinfunction "2_2") (pintype "passive"))
    )
    (net (code "153") (name "VTP") (class "Default")
      (node (ref "K16") (pin "2") (pinfunction "-IN1_2") (pintype "bidirectional"))
      (node (ref "R52") (pin "1") (pinfunction "1_1") (pintype "passive"))
      (node (ref "R53") (pin "1") (pinfunction "1_1") (pintype "passive"))
    )
    (net (code "154") (name "unconnected-(CAN-Pad2)") (class "Default")
      (node (ref "CAN") (pin "2") (pinfunction "2_2") (pintype "passive"))
    )
    (net (code "155") (name "unconnected-(JTAG1-Pad6)") (class "Default")
      (node (ref "JTAG1") (pin "6") (pinfunction "6_6") (pintype "bidirectional"))
    )
    (net (code "156") (name "unconnected-(JTAG1-Pad7)") (class "Default")
      (node (ref "JTAG1") (pin "7") (pinfunction "7_7") (pintype "bidirectional"))
    )
    (net (code "157") (name "unconnected-(K1-NC-Pad1)") (class "Default")
      (node (ref "K1") (pin "1") (pinfunction "NC_1") (pintype "no_connect"))
    )
    (net (code "158") (name "unconnected-(K2-PGOOD-Pad10)") (class "Default")
      (node (ref "K2") (pin "10") (pinfunction "PGOOD_10") (pintype "output"))
    )
    (net (code "159") (name "unconnected-(K15-PGOOD-Pad10)") (class "Default")
      (node (ref "K15") (pin "10") (pinfunction "PGOOD_10") (pintype "output"))
    )
    (net (code "160") (name "unconnected-(K17-NC-Pad5)") (class "Default")
      (node (ref "K17") (pin "5") (pinfunction "NC_5") (pintype "no_connect"))
    )
    (net (code "161") (name "unconnected-(K20-TAP_1-Pad7)") (class "Default")
      (node (ref "K20") (pin "7") (pinfunction "TAP_1_7") (pintype "output"))
    )
    (net (code "162") (name "unconnected-(K20-TAP_2-Pad2)") (class "Default")
      (node (ref "K20") (pin "2") (pinfunction "TAP_2_2") (pintype "output"))
    )
    (net (code "163") (name "unconnected-(K20-TAP_3-Pad6)") (class "Default")
      (node (ref "K20") (pin "6") (pinfunction "TAP_3_6") (pintype "output"))
    )
    (net (code "164") (name "unconnected-(K20-TAP_4-Pad3)") (class "Default")
      (node (ref "K20") (pin "3") (pinfunction "TAP_4_3") (pintype "output"))
    )
    (net (code "165") (name "unconnected-(K23-NC-Pad1)") (class "Default")
      (node (ref "K23") (pin "1") (pinfunction "NC_1") (pintype "passive"))
    )
    (net (code "166") (name "unconnected-(K29-NC-Pad5)") (class "Default")
      (node (ref "K29") (pin "5") (pinfunction "NC_5") (pintype "no_connect"))
    )
    (net (code "167") (name "unconnected-(REF1-Pad1)") (class "Default")
      (node (ref "REF1") (pin "1") (pinfunction "1_1") (pintype "passive"))
    )
    (net (code "168") (name "unconnected-(U$3-PadP$33)") (class "Default")
      (node (ref "U$3") (pin "P$33") (pinfunction "P$33_P$33") (pintype "bidirectional"))
    )
    (net (code "169") (name "unconnected-(U$3-PadP$34)") (class "Default")
      (node (ref "U$3") (pin "P$34") (pinfunction "P$34_P$34") (pintype "bidirectional"))
    )
    (net (code "170") (name "unconnected-(U$3-PadP$35)") (class "Default")
      (node (ref "U$3") (pin "P$35") (pinfunction "P$35_P$35") (pintype "bidirectional"))
    )
    (net (code "171") (name "unconnected-(U$3-PadP$36)") (class "Default")
      (node (ref "U$3") (pin "P$36") (pinfunction "P$36_P$36") (pintype "bidirectional"))
    )
    (net (code "172") (name "unconnected-(U$3-PadP$37)") (class "Default")
      (node (ref "U$3") (pin "P$37") (pinfunction "P$37_P$37") (pintype "bidirectional"))
    )
    (net (code "173") (name "unconnected-(U$3-PadP$38)") (class "Default")
      (node (ref "U$3") (pin "P$38") (pinfunction "P$38_P$38") (pintype "bidirectional"))
    )
    (net (code "174") (name "unconnected-(U$3-PadP$39)") (class "Default")
      (node (ref "U$3") (pin "P$39") (pinfunction "P$39_P$39") (pintype "bidirectional"))
    )
    (net (code "175") (name "unconnected-(U$3-PadP$40)") (class "Default")
      (node (ref "U$3") (pin "P$40") (pinfunction "P$40_P$40") (pintype "bidirectional"))
    )
    (net (code "176") (name "unconnected-(U$4-PadP$33)") (class "Default")
      (node (ref "U$4") (pin "P$33") (pinfunction "P$33_P$33") (pintype "bidirectional"))
    )
    (net (code "177") (name "unconnected-(U$4-PadP$34)") (class "Default")
      (node (ref "U$4") (pin "P$34") (pinfunction "P$34_P$34") (pintype "bidirectional"))
    )
    (net (code "178") (name "unconnected-(U$4-PadP$35)") (class "Default")
      (node (ref "U$4") (pin "P$35") (pinfunction "P$35_P$35") (pintype "bidirectional"))
    )
    (net (code "179") (name "unconnected-(U$4-PadP$36)") (class "Default")
      (node (ref "U$4") (pin "P$36") (pinfunction "P$36_P$36") (pintype "bidirectional"))
    )
    (net (code "180") (name "unconnected-(U$4-PadP$37)") (class "Default")
      (node (ref "U$4") (pin "P$37") (pinfunction "P$37_P$37") (pintype "bidirectional"))
    )
    (net (code "181") (name "unconnected-(U$4-PadP$38)") (class "Default")
      (node (ref "U$4") (pin "P$38") (pinfunction "P$38_P$38") (pintype "bidirectional"))
    )
    (net (code "182") (name "unconnected-(U$4-PadP$39)") (class "Default")
      (node (ref "U$4") (pin "P$39") (pinfunction "P$39_P$39") (pintype "bidirectional"))
    )
    (net (code "183") (name "unconnected-(U$4-PadP$40)") (class "Default")
      (node (ref "U$4") (pin "P$40") (pinfunction "P$40_P$40") (pintype "bidirectional"))
    )
    (net (code "184") (name "unconnected-(U$10-ELEC_TEST-PadL17)") (class "Default")
      (node (ref "U$10") (pin "L17") (pinfunction "ELEC_TEST_L17") (pintype "input"))
    )
    (net (code "185") (name "unconnected-(U$10-MISO--PadN13)") (class "Default")
      (node (ref "U$10") (pin "N13") (pinfunction "MISO-_N13") (pintype "output"))
    )
    (net (code "186") (name "unconnected-(U$10-MOSI--PadN11)") (class "Default")
      (node (ref "U$10") (pin "N11") (pinfunction "MOSI-_N11") (pintype "input"))
    )
    (net (code "187") (name "unconnected-(U$10-NC1-PadK1)") (class "Default")
      (node (ref "U$10") (pin "K1") (pinfunction "NC1_K1") (pintype "no_connect"))
    )
    (net (code "188") (name "unconnected-(U$10-NC2-PadK17)") (class "Default")
      (node (ref "U$10") (pin "K17") (pinfunction "NC2_K17") (pintype "no_connect"))
    )
    (net (code "189") (name "unconnected-(U$10-NC3-PadL1)") (class "Default")
      (node (ref "U$10") (pin "L1") (pinfunction "NC3_L1") (pintype "no_connect"))
    )
    (net (code "190") (name "unconnected-(U$10-NC4-PadL2)") (class "Default")
      (node (ref "U$10") (pin "L2") (pinfunction "NC4_L2") (pintype "no_connect"))
    )
    (net (code "191") (name "unconnected-(U$10-NC5-PadL16)") (class "Default")
      (node (ref "U$10") (pin "L16") (pinfunction "NC5_L16") (pintype "no_connect"))
    )
    (net (code "192") (name "unconnected-(U$10-NC6-PadM3)") (class "Default")
      (node (ref "U$10") (pin "M3") (pinfunction "NC6_M3") (pintype "no_connect"))
    )
    (net (code "193") (name "unconnected-(U$10-NC7-PadM4)") (class "Default")
      (node (ref "U$10") (pin "M4") (pinfunction "NC7_M4") (pintype "no_connect"))
    )
    (net (code "194") (name "unconnected-(U$10-NC8-PadM5)") (class "Default")
      (node (ref "U$10") (pin "M5") (pinfunction "NC8_M5") (pintype "no_connect"))
    )
    (net (code "195") (name "unconnected-(U$10-NC9-PadM6)") (class "Default")
      (node (ref "U$10") (pin "M6") (pinfunction "NC9_M6") (pintype "no_connect"))
    )
    (net (code "196") (name "unconnected-(U$10-NC10-PadM7)") (class "Default")
      (node (ref "U$10") (pin "M7") (pinfunction "NC10_M7") (pintype "no_connect"))
    )
    (net (code "197") (name "unconnected-(U$10-NC11-PadM8)") (class "Default")
      (node (ref "U$10") (pin "M8") (pinfunction "NC11_M8") (pintype "no_connect"))
    )
    (net (code "198") (name "unconnected-(U$10-NC12-PadM9)") (class "Default")
      (node (ref "U$10") (pin "M9") (pinfunction "NC12_M9") (pintype "no_connect"))
    )
    (net (code "199") (name "unconnected-(U$10-NC13-PadM10)") (class "Default")
      (node (ref "U$10") (pin "M10") (pinfunction "NC13_M10") (pintype "no_connect"))
    )
    (net (code "200") (name "unconnected-(U$10-NC14-PadM11)") (class "Default")
      (node (ref "U$10") (pin "M11") (pinfunction "NC14_M11") (pintype "no_connect"))
    )
    (net (code "201") (name "unconnected-(U$10-NC15-PadM12)") (class "Default")
      (node (ref "U$10") (pin "M12") (pinfunction "NC15_M12") (pintype "no_connect"))
    )
    (net (code "202") (name "unconnected-(U$10-NC16-PadM13)") (class "Default")
      (node (ref "U$10") (pin "M13") (pinfunction "NC16_M13") (pintype "no_connect"))
    )
    (net (code "203") (name "unconnected-(U$10-NC17-PadM14)") (class "Default")
      (node (ref "U$10") (pin "M14") (pinfunction "NC17_M14") (pintype "no_connect"))
    )
    (net (code "204") (name "unconnected-(U$10-SCLK--PadN9)") (class "Default")
      (node (ref "U$10") (pin "N9") (pinfunction "SCLK-_N9") (pintype "input"))
    )
    (net (code "205") (name "unconnected-(U$10-~{CS}--PadN7)") (class "Default")
      (node (ref "U$10") (pin "N7") (pinfunction "~{CS}-_N7") (pintype "input"))
    )
    (net (code "206") (name "unconnected-(U2A-PA0-PadG2)") (class "Default")
      (node (ref "U2") (pin "G2") (pinfunction "PA0_G2") (pintype "bidirectional"))
    )
    (net (code "207") (name "unconnected-(U2A-PA1-PadH2)") (class "Default")
      (node (ref "U2") (pin "H2") (pinfunction "PA1_H2") (pintype "bidirectional"))
    )
    (net (code "208") (name "unconnected-(U2A-PA2-PadF3)") (class "Default")
      (node (ref "U2") (pin "F3") (pinfunction "PA2_F3") (pintype "bidirectional"))
    )
    (net (code "209") (name "unconnected-(U2A-PA3-PadG3)") (class "Default")
      (node (ref "U2") (pin "G3") (pinfunction "PA3_G3") (pintype "bidirectional"))
    )
    (net (code "210") (name "unconnected-(U2A-PA5-PadF4)") (class "Default")
      (node (ref "U2") (pin "F4") (pinfunction "PA5_F4") (pintype "bidirectional"))
    )
    (net (code "211") (name "unconnected-(U2A-PA6-PadG4)") (class "Default")
      (node (ref "U2") (pin "G4") (pinfunction "PA6_G4") (pintype "bidirectional"))
    )
    (net (code "212") (name "unconnected-(U2A-PA8-PadD7)") (class "Default")
      (node (ref "U2") (pin "D7") (pinfunction "PA8_D7") (pintype "bidirectional"))
    )
    (net (code "213") (name "unconnected-(U2A-PA9-PadC7)") (class "Default")
      (node (ref "U2") (pin "C7") (pinfunction "PA9_C7") (pintype "bidirectional"))
    )
    (net (code "214") (name "unconnected-(U2A-PA10-PadC6)") (class "Default")
      (node (ref "U2") (pin "C6") (pinfunction "PA10_C6") (pintype "bidirectional"))
    )
    (net (code "215") (name "unconnected-(U2A-PB0-PadF5)") (class "Default")
      (node (ref "U2") (pin "F5") (pinfunction "PB0_F5") (pintype "bidirectional"))
    )
    (net (code "216") (name "unconnected-(U2A-PB1-PadG5)") (class "Default")
      (node (ref "U2") (pin "G5") (pinfunction "PB1_G5") (pintype "bidirectional"))
    )
    (net (code "217") (name "unconnected-(U2A-PB2-PadG6)") (class "Default")
      (node (ref "U2") (pin "G6") (pinfunction "PB2_G6") (pintype "bidirectional"))
    )
    (net (code "218") (name "unconnected-(U2A-PB5-PadC4)") (class "Default")
      (node (ref "U2") (pin "C4") (pinfunction "PB5_C4") (pintype "bidirectional"))
    )
    (net (code "219") (name "unconnected-(U2A-PB6-PadD3)") (class "Default")
      (node (ref "U2") (pin "D3") (pinfunction "PB6_D3") (pintype "bidirectional"))
    )
    (net (code "220") (name "unconnected-(U2A-PB7-PadC3)") (class "Default")
      (node (ref "U2") (pin "C3") (pinfunction "PB7_C3") (pintype "bidirectional"))
    )
    (net (code "221") (name "unconnected-(U2A-PB11-PadH7)") (class "Default")
      (node (ref "U2") (pin "H7") (pinfunction "PB11_H7") (pintype "bidirectional"))
    )
    (net (code "222") (name "unconnected-(U2A-PC0-PadE3)") (class "Default")
      (node (ref "U2") (pin "E3") (pinfunction "PC0_E3") (pintype "bidirectional"))
    )
    (net (code "223") (name "unconnected-(U2A-PC1-PadE2)") (class "Default")
      (node (ref "U2") (pin "E2") (pinfunction "PC1_E2") (pintype "bidirectional"))
    )
    (net (code "224") (name "unconnected-(U2A-PC3-PadG1)") (class "Default")
      (node (ref "U2") (pin "G1") (pinfunction "PC3_G1") (pintype "bidirectional"))
    )
    (net (code "225") (name "unconnected-(U2A-PC6-PadF6)") (class "Default")
      (node (ref "U2") (pin "F6") (pinfunction "PC6_F6") (pintype "bidirectional"))
    )
    (net (code "226") (name "unconnected-(U2A-PC7-PadE7)") (class "Default")
      (node (ref "U2") (pin "E7") (pinfunction "PC7_E7") (pintype "bidirectional"))
    )
    (net (code "227") (name "unconnected-(U2A-PC8-PadE8)") (class "Default")
      (node (ref "U2") (pin "E8") (pinfunction "PC8_E8") (pintype "bidirectional"))
    )
    (net (code "228") (name "unconnected-(U2A-PD2-PadB5)") (class "Default")
      (node (ref "U2") (pin "B5") (pinfunction "PD2_B5") (pintype "bidirectional"))
    )
    (net (code "229") (name "unconnected-(U2A-PH3-BOOT0-PadB4)") (class "Default")
      (node (ref "U2") (pin "B4") (pinfunction "PH3-BOOT0_B4") (pintype "bidirectional"))
    )
  )
)
